# PSPS_AVNC_SRD_fullBoard-2020-09-19.net
KiCad netlist of a schematic drawn in EAGLE
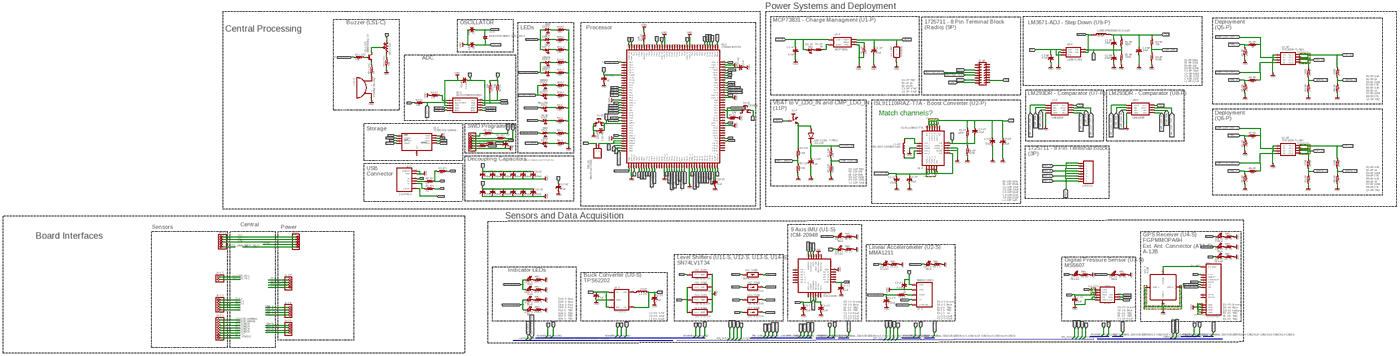
[diagram p0: schematic, sheet 1, overview]
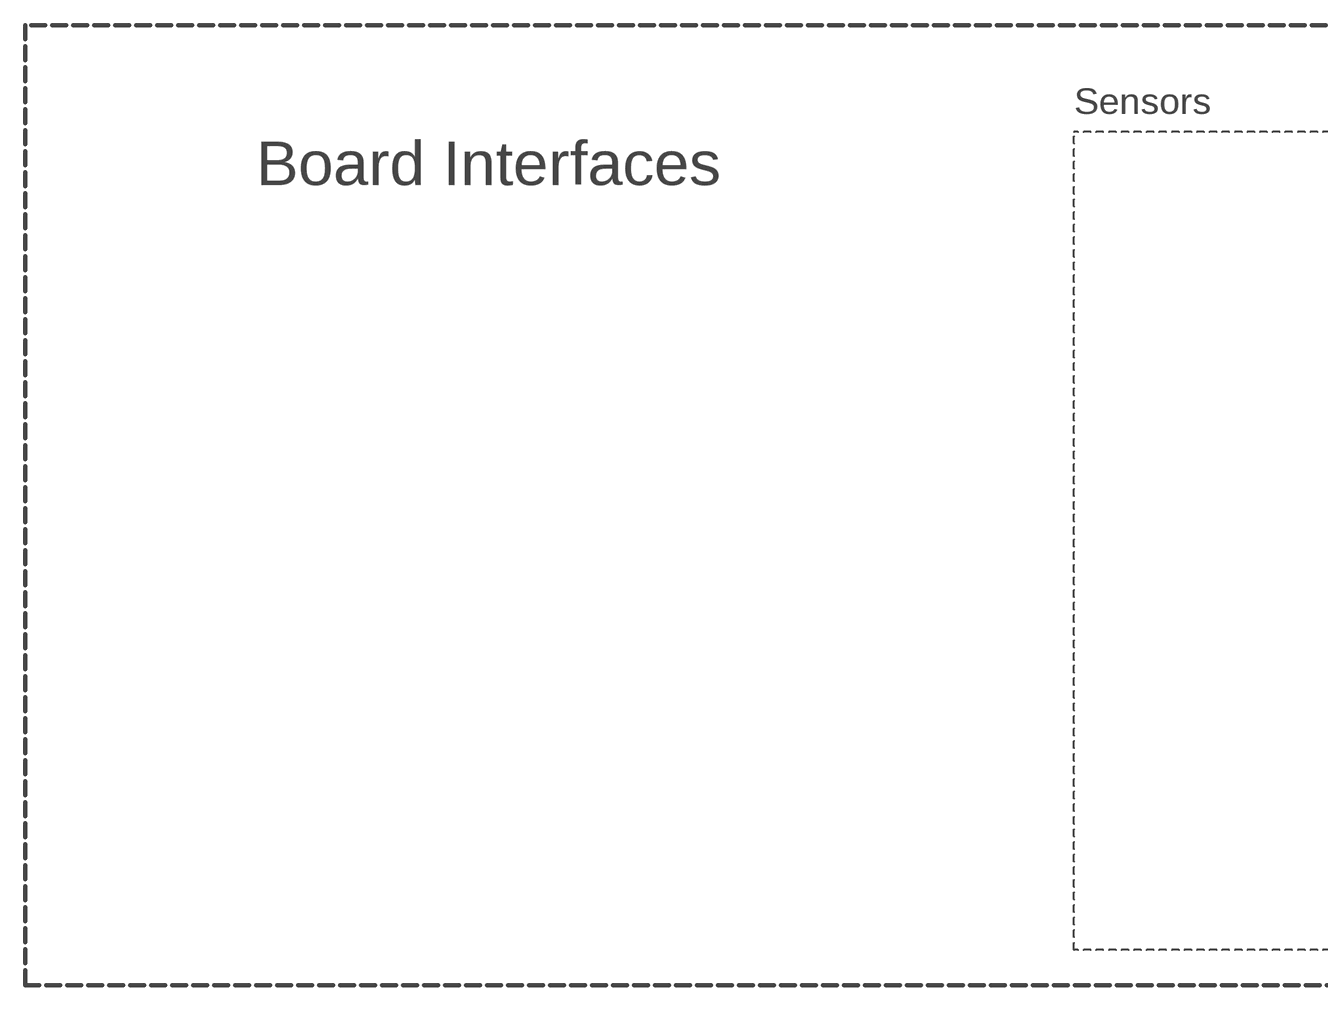
[diagram p1: schematic, sheet 1, part 1 of 4]
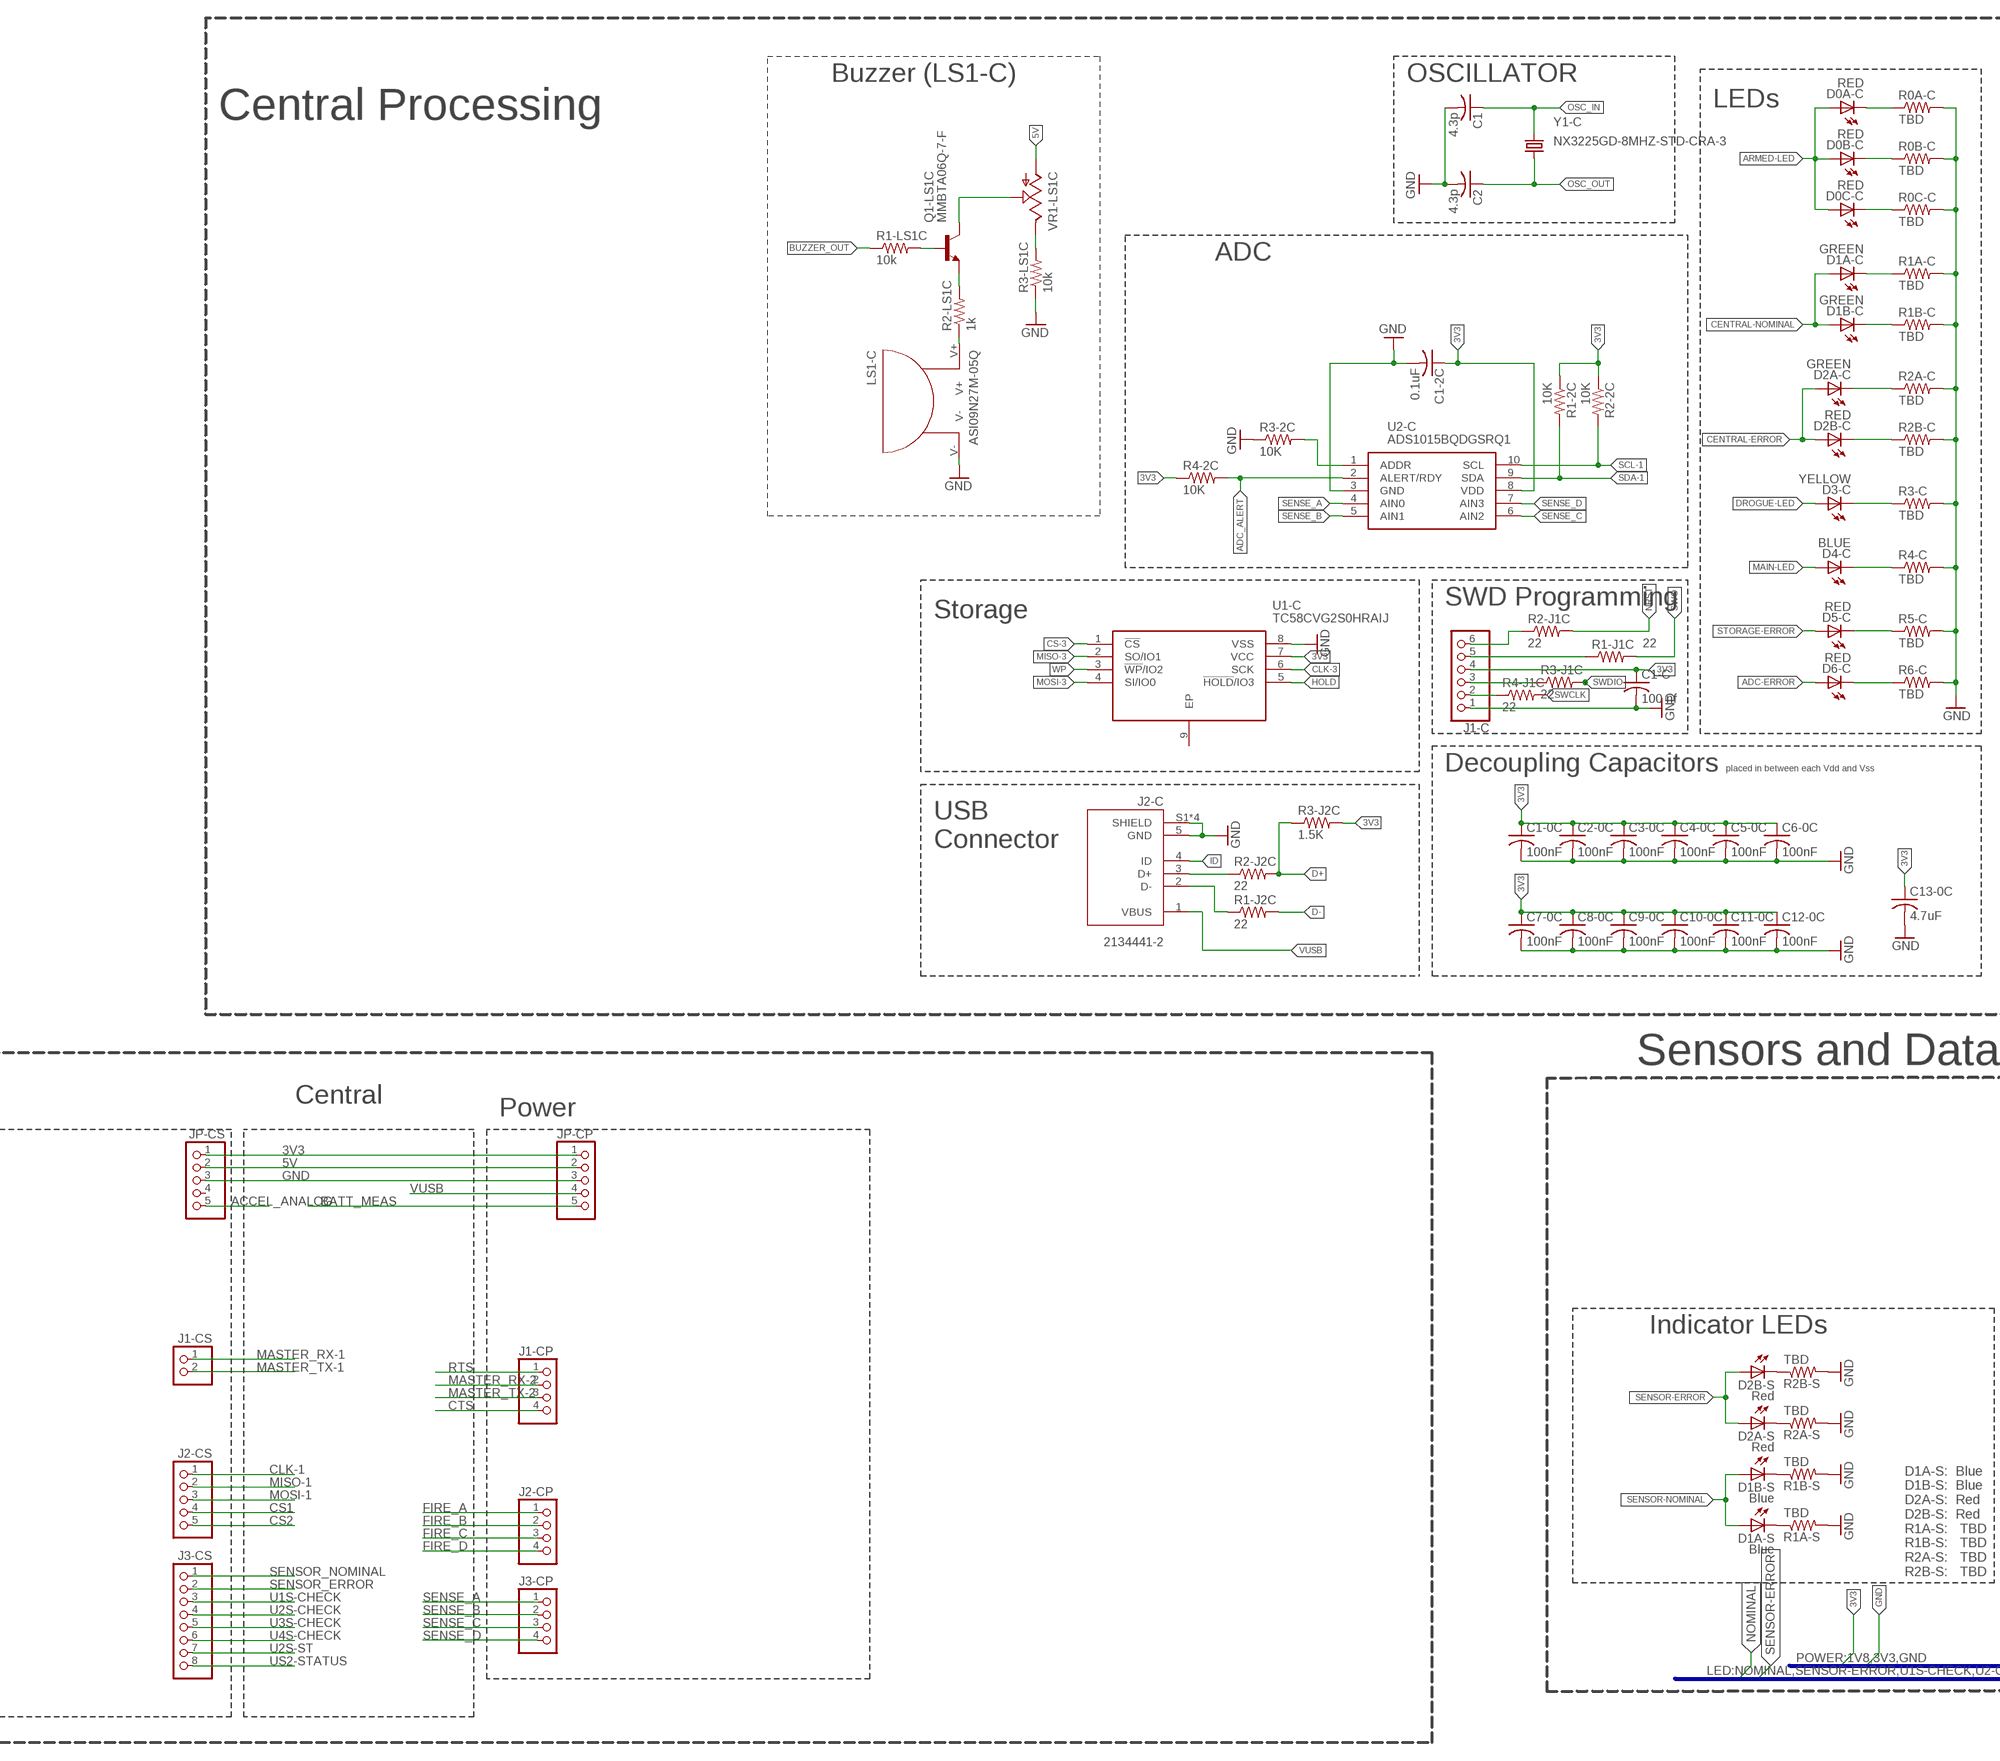
[diagram p2: schematic, sheet 1, part 2 of 4]
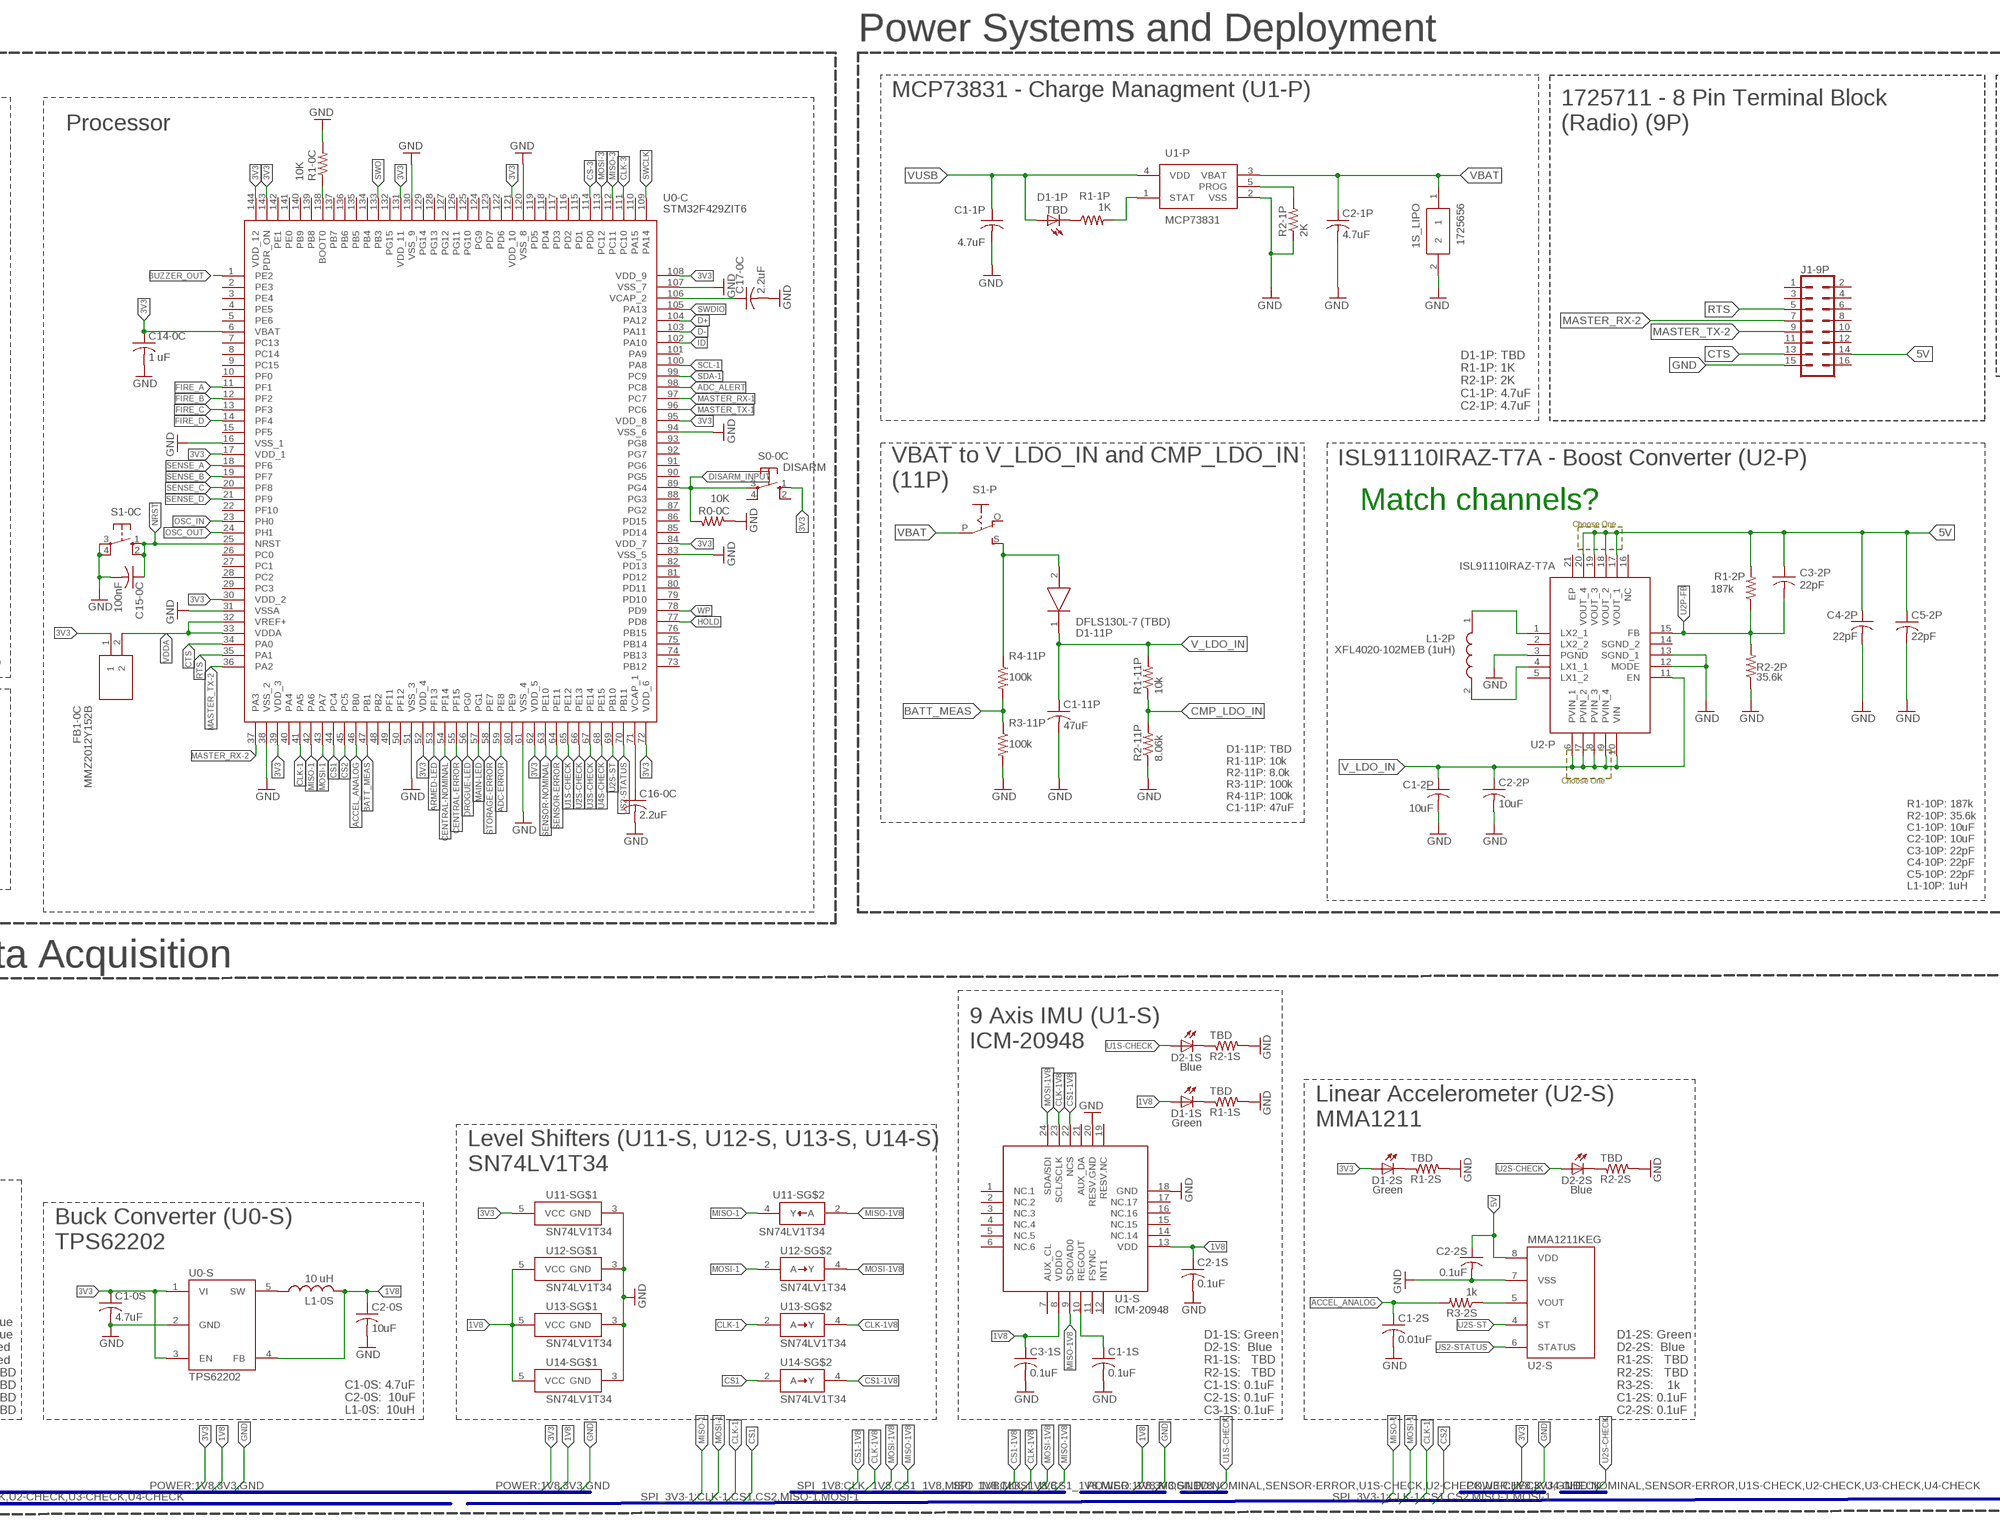
[diagram p3: schematic, sheet 1, part 3 of 4]
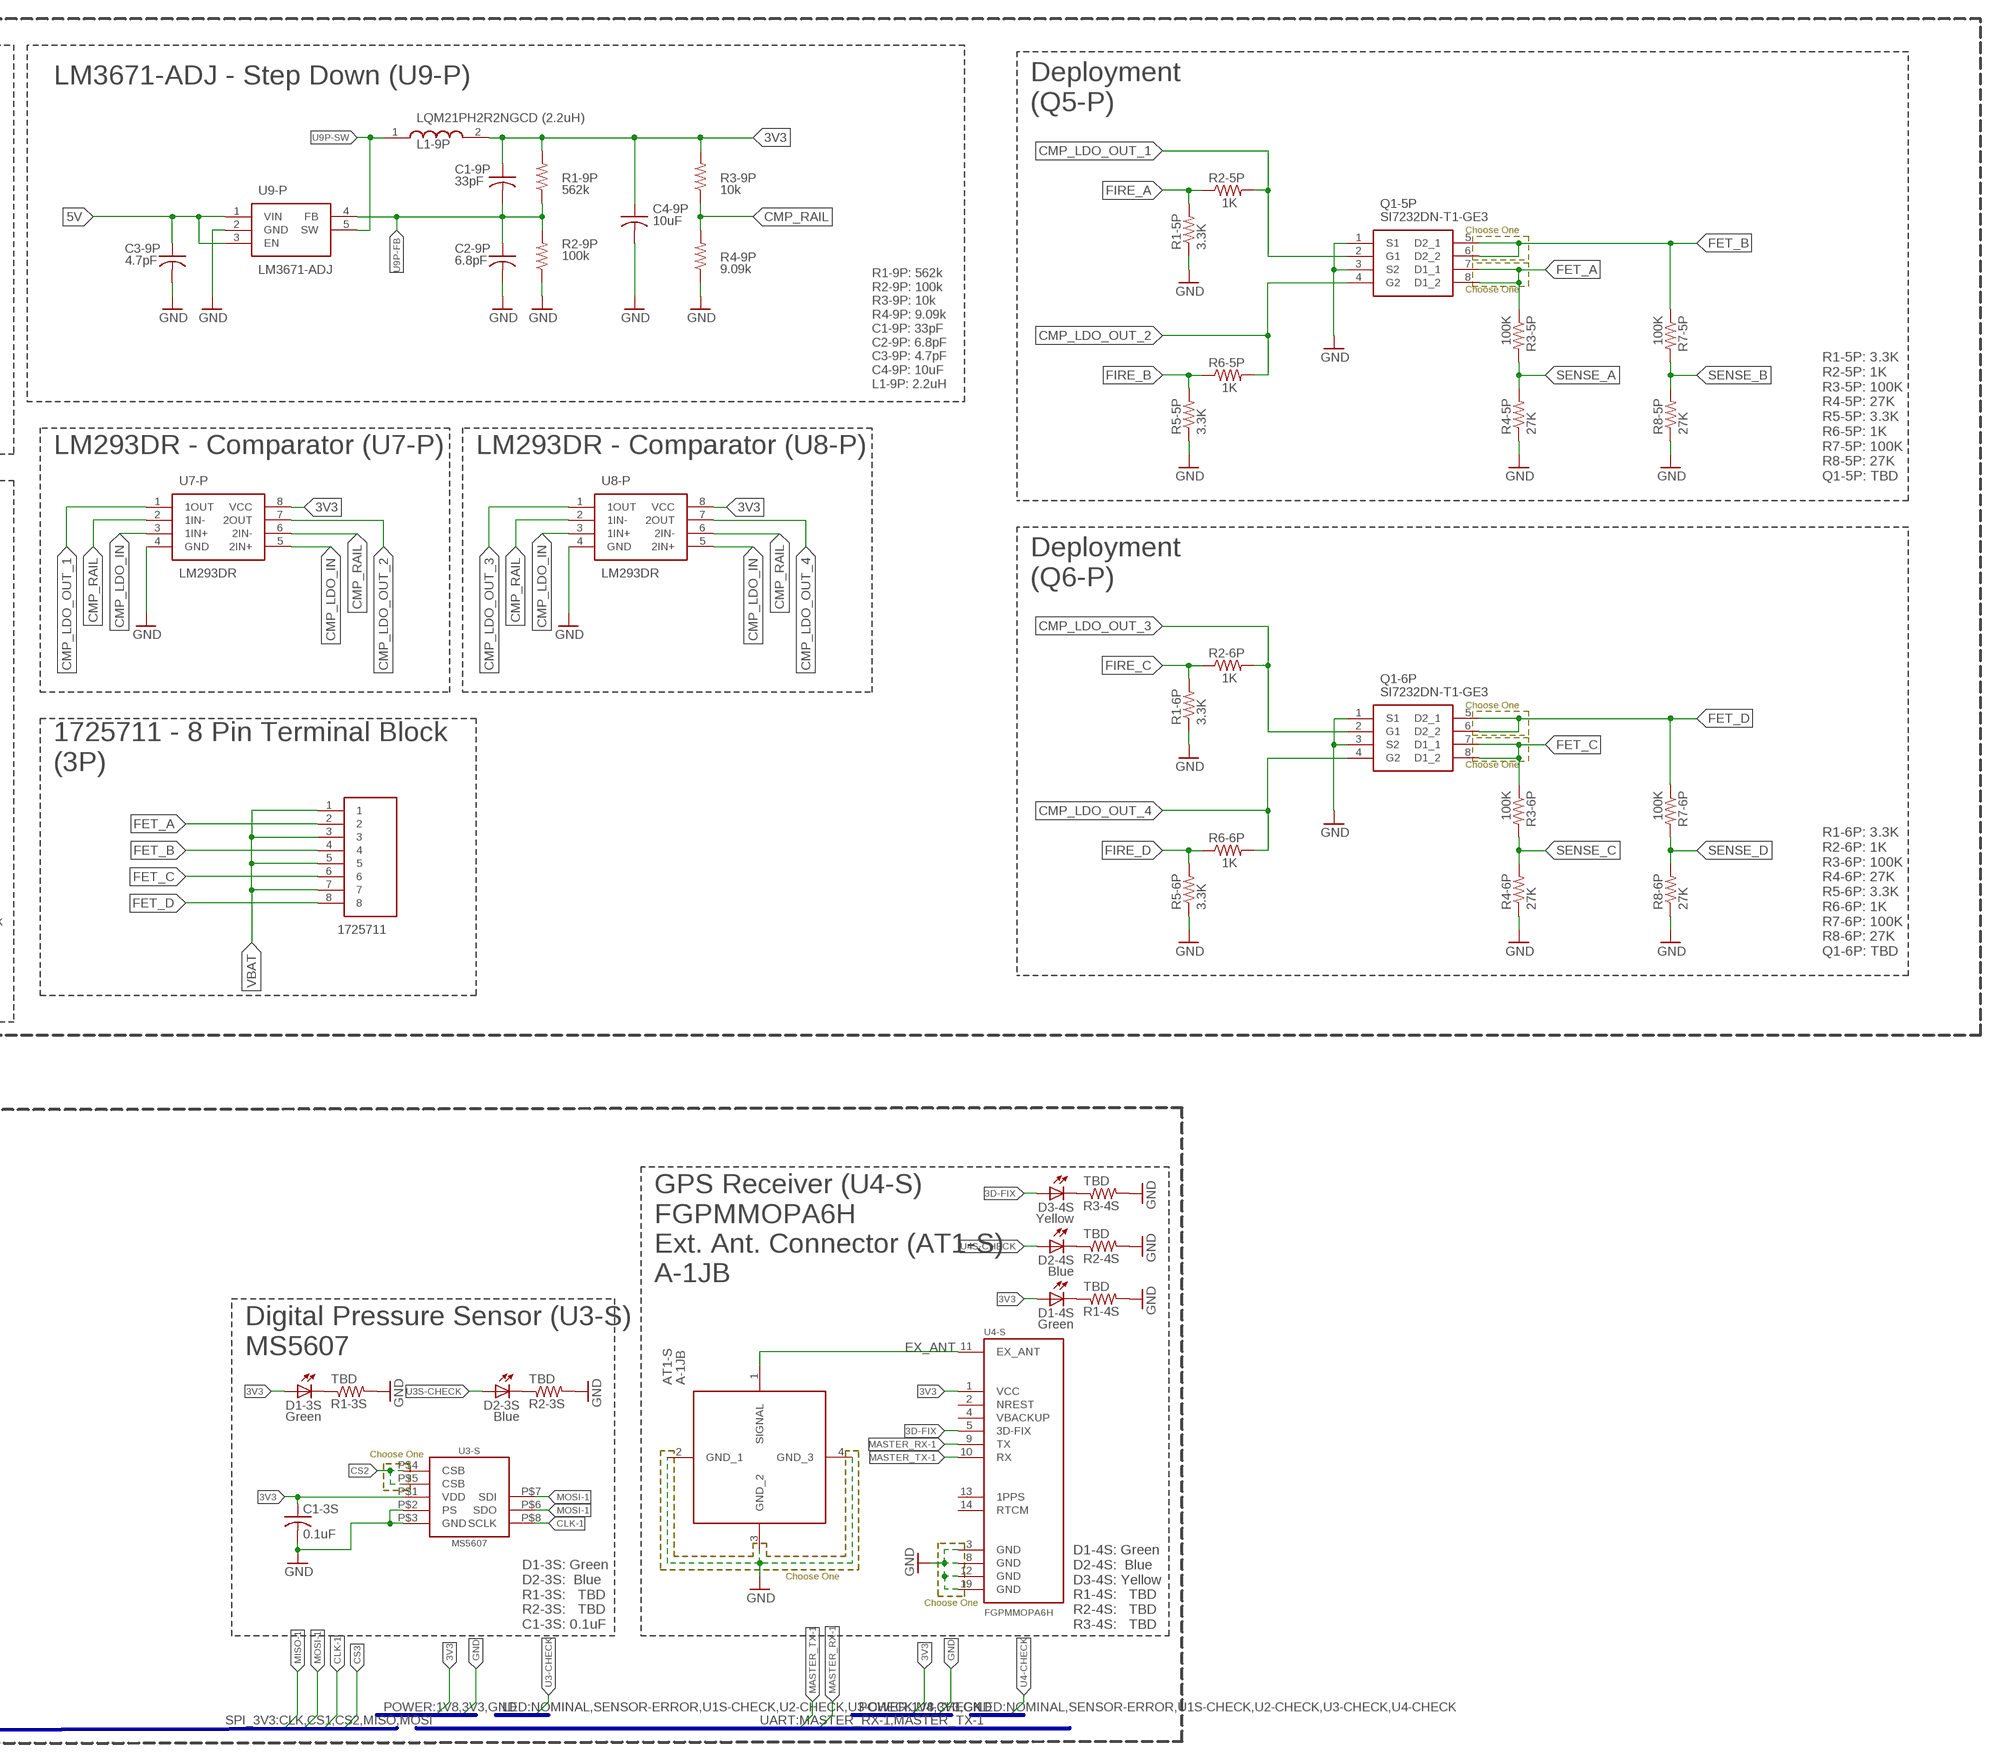
[diagram p4: schematic, sheet 1, part 4 of 4]

(export (version "E")
  (design (tool "Eeschema 10.0.6"))
  (components
    (comp (ref "1S_LIPO")
      (value "1725656")
      (footprint "eagle-import:1725656")
      (fields (field (name "MOUSER_PART_NUMBER") "651-1725656"))
      (libsource (lib "eagle-import") (part "1725656"))
    )
    (comp (ref "AT1-S")
      (value "A-1JB")
      (footprint "eagle-import:A1JB")
      (fields (field (name "MOUSER_PART_NUMBER") "523-A-1JB"))
      (libsource (lib "eagle-import") (part "A-1JB"))
    )
    (comp (ref "C1")
      (value "4.3p")
      (footprint "eagle-import:C0805")
      (libsource (lib "eagle-import") (part "rcl_334_C-USC0805"))
    )
    (comp (ref "C1-0C")
      (value "100nF")
      (footprint "eagle-import:C0805")
      (libsource (lib "eagle-import") (part "rcl_334_C-USC0805"))
    )
    (comp (ref "C1-0S")
      (value "4.7uF")
      (footprint "eagle-import:C0805")
      (libsource (lib "eagle-import") (part "resistor_348_C-USC0805"))
    )
    (comp (ref "C1-1P")
      (value "4.7uF")
      (footprint "eagle-import:C0805")
      (libsource (lib "eagle-import") (part "resistor_348_C-USC0805"))
    )
    (comp (ref "C1-1S")
      (value "0.1uF")
      (footprint "eagle-import:C0805")
      (libsource (lib "eagle-import") (part "resistor_348_C-USC0805"))
    )
    (comp (ref "C1-2C")
      (value "0.1uF")
      (footprint "eagle-import:C0805")
      (libsource (lib "eagle-import") (part "rcl_334_C-USC0805"))
    )
    (comp (ref "C1-2P")
      (value "10uF")
      (footprint "eagle-import:C0805")
      (libsource (lib "eagle-import") (part "resistor_348_C-USC0805"))
    )
    (comp (ref "C1-2S")
      (value "0.01uF")
      (footprint "eagle-import:C0805")
      (libsource (lib "eagle-import") (part "resistor_348_C-USC0805"))
    )
    (comp (ref "C1-3S")
      (value "0.1uF")
      (footprint "eagle-import:C0805")
      (libsource (lib "eagle-import") (part "resistor_348_C-USC0805"))
    )
    (comp (ref "C1-9P")
      (value "33pF")
      (footprint "eagle-import:C0805")
      (libsource (lib "eagle-import") (part "resistor_348_C-USC0805"))
    )
    (comp (ref "C1-11P")
      (value "47uF")
      (footprint "eagle-import:C0805")
      (libsource (lib "eagle-import") (part "resistor_348_C-USC0805"))
    )
    (comp (ref "C1-C")
      (value "100 nf")
      (footprint "eagle-import:C0805")
      (libsource (lib "eagle-import") (part "rcl_334_C-USC0805"))
    )
    (comp (ref "C2")
      (value "4.3p")
      (footprint "eagle-import:C0805")
      (libsource (lib "eagle-import") (part "rcl_334_C-USC0805"))
    )
    (comp (ref "C2-0C")
      (value "100nF")
      (footprint "eagle-import:C0805")
      (libsource (lib "eagle-import") (part "rcl_334_C-USC0805"))
    )
    (comp (ref "C2-0S")
      (value "10uF")
      (footprint "eagle-import:C0805")
      (libsource (lib "eagle-import") (part "resistor_348_C-USC0805"))
    )
    (comp (ref "C2-1P")
      (value "4.7uF")
      (footprint "eagle-import:C0805")
      (libsource (lib "eagle-import") (part "resistor_348_C-USC0805"))
    )
    (comp (ref "C2-1S")
      (value "0.1uF")
      (footprint "eagle-import:C0805")
      (libsource (lib "eagle-import") (part "resistor_348_C-USC0805"))
    )
    (comp (ref "C2-2P")
      (value "10uF")
      (footprint "eagle-import:C0805")
      (libsource (lib "eagle-import") (part "C-USC0805"))
    )
    (comp (ref "C2-2S")
      (value "0.1uF")
      (footprint "eagle-import:C0805")
      (libsource (lib "eagle-import") (part "resistor_348_C-USC0805"))
    )
    (comp (ref "C2-9P")
      (value "6.8pF")
      (footprint "eagle-import:C0805")
      (libsource (lib "eagle-import") (part "resistor_348_C-USC0805"))
    )
    (comp (ref "C3-0C")
      (value "100nF")
      (footprint "eagle-import:C0805")
      (libsource (lib "eagle-import") (part "rcl_334_C-USC0805"))
    )
    (comp (ref "C3-1S")
      (value "0.1uF")
      (footprint "eagle-import:C0805")
      (libsource (lib "eagle-import") (part "resistor_348_C-USC0805"))
    )
    (comp (ref "C3-2P")
      (value "22pF")
      (footprint "eagle-import:C0805")
      (libsource (lib "eagle-import") (part "resistor_348_C-USC0805"))
    )
    (comp (ref "C3-9P")
      (value "4.7pF")
      (footprint "eagle-import:C0805")
      (libsource (lib "eagle-import") (part "resistor_348_C-USC0805"))
    )
    (comp (ref "C4-0C")
      (value "100nF")
      (footprint "eagle-import:C0805")
      (libsource (lib "eagle-import") (part "rcl_334_C-USC0805"))
    )
    (comp (ref "C4-2P")
      (value "22pF")
      (footprint "eagle-import:C0805")
      (fields (field (name "SPICEPREFIX") "C"))
      (libsource (lib "eagle-import") (part "resistor_348_C-USC0805"))
    )
    (comp (ref "C4-9P")
      (value "10uF")
      (footprint "eagle-import:C0805")
      (libsource (lib "eagle-import") (part "resistor_348_C-USC0805"))
    )
    (comp (ref "C5-0C")
      (value "100nF")
      (footprint "eagle-import:C0805")
      (libsource (lib "eagle-import") (part "rcl_334_C-USC0805"))
    )
    (comp (ref "C5-2P")
      (value "22pF")
      (footprint "eagle-import:C0805")
      (libsource (lib "eagle-import") (part "C-USC0805"))
    )
    (comp (ref "C6-0C")
      (value "100nF")
      (footprint "eagle-import:C0805")
      (libsource (lib "eagle-import") (part "rcl_334_C-USC0805"))
    )
    (comp (ref "C7-0C")
      (value "100nF")
      (footprint "eagle-import:C0805")
      (libsource (lib "eagle-import") (part "rcl_334_C-USC0805"))
    )
    (comp (ref "C8-0C")
      (value "100nF")
      (footprint "eagle-import:C0805")
      (libsource (lib "eagle-import") (part "rcl_334_C-USC0805"))
    )
    (comp (ref "C9-0C")
      (value "100nF")
      (footprint "eagle-import:C0805")
      (libsource (lib "eagle-import") (part "rcl_334_C-USC0805"))
    )
    (comp (ref "C10-0C")
      (value "100nF")
      (footprint "eagle-import:C0805")
      (libsource (lib "eagle-import") (part "rcl_334_C-USC0805"))
    )
    (comp (ref "C11-0C")
      (value "100nF")
      (footprint "eagle-import:C0805")
      (libsource (lib "eagle-import") (part "rcl_334_C-USC0805"))
    )
    (comp (ref "C12-0C")
      (value "100nF")
      (footprint "eagle-import:C0805")
      (libsource (lib "eagle-import") (part "rcl_334_C-USC0805"))
    )
    (comp (ref "C13-0C")
      (value "4.7uF")
      (footprint "eagle-import:C0805")
      (libsource (lib "eagle-import") (part "rcl_334_C-USC0805"))
    )
    (comp (ref "C14-0C")
      (value "1 uF")
      (footprint "eagle-import:C0805")
      (libsource (lib "eagle-import") (part "rcl_334_C-USC0805"))
    )
    (comp (ref "C15-0C")
      (value "100nF")
      (footprint "eagle-import:C0805")
      (libsource (lib "eagle-import") (part "rcl_334_C-USC0805"))
    )
    (comp (ref "C16-0C")
      (value "2.2uF")
      (footprint "eagle-import:C0805")
      (libsource (lib "eagle-import") (part "rcl_334_C-USC0805"))
    )
    (comp (ref "C17-0C")
      (value "2.2uF")
      (footprint "eagle-import:C0805")
      (libsource (lib "eagle-import") (part "rcl_334_C-USC0805"))
    )
    (comp (ref "D0A-C")
      (value "RED")
      (footprint "eagle-import:CHIPLED_0805")
      (libsource (lib "eagle-import") (part "adafruit_420_LEDCHIPLED_0805"))
    )
    (comp (ref "D0B-C")
      (value "RED")
      (footprint "eagle-import:CHIPLED_0805")
      (libsource (lib "eagle-import") (part "adafruit_420_LEDCHIPLED_0805"))
    )
    (comp (ref "D0C-C")
      (value "RED")
      (footprint "eagle-import:CHIPLED_0805")
      (libsource (lib "eagle-import") (part "adafruit_420_LEDCHIPLED_0805"))
    )
    (comp (ref "D1-1P")
      (value "TBD")
      (footprint "eagle-import:CHIPLED_0805")
      (libsource (lib "eagle-import") (part "adafruit_420_LEDCHIPLED_0805"))
    )
    (comp (ref "D1-1S")
      (value "Green")
      (footprint "eagle-import:CHIPLED_0805")
      (libsource (lib "eagle-import") (part "LEDCHIPLED_0805"))
    )
    (comp (ref "D1-2S")
      (value "Green")
      (footprint "eagle-import:CHIPLED_0805")
      (libsource (lib "eagle-import") (part "LEDCHIPLED_0805"))
    )
    (comp (ref "D1-3S")
      (value "Green")
      (footprint "eagle-import:CHIPLED_0805")
      (libsource (lib "eagle-import") (part "LEDCHIPLED_0805"))
    )
    (comp (ref "D1-4S")
      (value "Green")
      (footprint "eagle-import:CHIPLED_0805")
      (libsource (lib "eagle-import") (part "LEDCHIPLED_0805"))
    )
    (comp (ref "D1-11P")
      (value "DFLS130L-7 (TBD)")
      (footprint "eagle-import:POWERDI_123")
      (fields
        (field (name "MANUFACTURER_PART_NUMBER") "DFLS130L-7")
        (field (name "MOUSER_PART_NUMBER") "621-DFLS130L")
      )
      (libsource (lib "eagle-import") (part "DFLS130L-7"))
    )
    (comp (ref "D1A-C")
      (value "GREEN")
      (footprint "eagle-import:CHIPLED_0805")
      (libsource (lib "eagle-import") (part "adafruit_420_LEDCHIPLED_0805"))
    )
    (comp (ref "D1A-S")
      (value "Blue")
      (footprint "eagle-import:CHIPLED_0805")
      (libsource (lib "eagle-import") (part "LEDCHIPLED_0805"))
    )
    (comp (ref "D1B-C")
      (value "GREEN")
      (footprint "eagle-import:CHIPLED_0805")
      (libsource (lib "eagle-import") (part "adafruit_420_LEDCHIPLED_0805"))
    )
    (comp (ref "D1B-S")
      (value "Blue")
      (footprint "eagle-import:CHIPLED_0805")
      (libsource (lib "eagle-import") (part "LEDCHIPLED_0805"))
    )
    (comp (ref "D2-1S")
      (value "Blue")
      (footprint "eagle-import:CHIPLED_0805")
      (libsource (lib "eagle-import") (part "LEDCHIPLED_0805"))
    )
    (comp (ref "D2-2S")
      (value "Blue")
      (footprint "eagle-import:CHIPLED_0805")
      (libsource (lib "eagle-import") (part "LEDCHIPLED_0805"))
    )
    (comp (ref "D2-3S")
      (value "Blue")
      (footprint "eagle-import:CHIPLED_0805")
      (libsource (lib "eagle-import") (part "LEDCHIPLED_0805"))
    )
    (comp (ref "D2-4S")
      (value "Blue")
      (footprint "eagle-import:CHIPLED_0805")
      (libsource (lib "eagle-import") (part "LEDCHIPLED_0805"))
    )
    (comp (ref "D2A-C")
      (value "GREEN")
      (footprint "eagle-import:CHIPLED_0805")
      (libsource (lib "eagle-import") (part "adafruit_420_LEDCHIPLED_0805"))
    )
    (comp (ref "D2A-S")
      (value "Red")
      (footprint "eagle-import:CHIPLED_0805")
      (libsource (lib "eagle-import") (part "LEDCHIPLED_0805"))
    )
    (comp (ref "D2B-C")
      (value "RED")
      (footprint "eagle-import:CHIPLED_0805")
      (libsource (lib "eagle-import") (part "adafruit_420_LEDCHIPLED_0805"))
    )
    (comp (ref "D2B-S")
      (value "Red")
      (footprint "eagle-import:CHIPLED_0805")
      (libsource (lib "eagle-import") (part "LEDCHIPLED_0805"))
    )
    (comp (ref "D3-4S")
      (value "Yellow")
      (footprint "eagle-import:CHIPLED_0805")
      (libsource (lib "eagle-import") (part "LEDCHIPLED_0805"))
    )
    (comp (ref "D3-C")
      (value "YELLOW")
      (footprint "eagle-import:CHIPLED_0805")
      (libsource (lib "eagle-import") (part "adafruit_420_LEDCHIPLED_0805"))
    )
    (comp (ref "D4-C")
      (value "BLUE")
      (footprint "eagle-import:CHIPLED_0805")
      (libsource (lib "eagle-import") (part "adafruit_420_LEDCHIPLED_0805"))
    )
    (comp (ref "D5-C")
      (value "RED")
      (footprint "eagle-import:CHIPLED_0805")
      (libsource (lib "eagle-import") (part "adafruit_420_LEDCHIPLED_0805"))
    )
    (comp (ref "D6-C")
      (value "RED")
      (footprint "eagle-import:CHIPLED_0805")
      (libsource (lib "eagle-import") (part "adafruit_420_LEDCHIPLED_0805"))
    )
    (comp (ref "FB1-0C")
      (value "MMZ2012Y152B")
      (footprint "eagle-import:BEADC2012X105N")
      (fields (field (name "MOUSER_PART_NUMBER") "810-MMZ2012Y152B"))
      (libsource (lib "eagle-import") (part "MMZ2012Y152B"))
    )
    (comp (ref "J1-9P")
      (value "CONN_08X2")
      (footprint "eagle-import:2X8")
      (libsource (lib "eagle-import") (part "CONN_08X2"))
    )
    (comp (ref "J1-C")
      (value "PINHD-1X6")
      (footprint "eagle-import:1X06")
      (libsource (lib "eagle-import") (part "PINHD-1X6"))
    )
    (comp (ref "J1-CP")
      (value "PINHD-1X4")
      (footprint "eagle-import:1X04")
      (libsource (lib "eagle-import") (part "PINHD-1X4"))
    )
    (comp (ref "J1-CS")
      (value "PINHD-1X2")
      (footprint "eagle-import:1X02")
      (libsource (lib "eagle-import") (part "PINHD-1X2"))
    )
    (comp (ref "J2-C")
      (value "2134441-2")
      (footprint "eagle-import:TE_2134441-2")
      (fields (field (name "DIGI-KEY_PART_NUMBER") "A118104CT-ND") (field (name "MF") "TE Connectivity"))
      (libsource (lib "eagle-import") (part "2134441-2"))
    )
    (comp (ref "J2-CP")
      (value "PINHD-1X4")
      (footprint "eagle-import:1X04")
      (libsource (lib "eagle-import") (part "PINHD-1X4"))
    )
    (comp (ref "J2-CS")
      (value "PINHD-1X5")
      (footprint "eagle-import:1X05")
      (libsource (lib "eagle-import") (part "PINHD-1X5"))
    )
    (comp (ref "J2-P")
      (value "1725711")
      (footprint "eagle-import:1725711")
      (fields (field (name "MOUSER_PART_NUMBER") "651-1725711"))
      (libsource (lib "eagle-import") (part "1725711"))
    )
    (comp (ref "J3-CP")
      (value "PINHD-1X4")
      (footprint "eagle-import:1X04")
      (libsource (lib "eagle-import") (part "PINHD-1X4"))
    )
    (comp (ref "J3-CS")
      (value "PINHD-1X8")
      (footprint "eagle-import:1X08")
      (libsource (lib "eagle-import") (part "PINHD-1X8"))
    )
    (comp (ref "JP-CP")
      (value "PINHD-1X5")
      (footprint "eagle-import:1X05")
      (libsource (lib "eagle-import") (part "PINHD-1X5"))
    )
    (comp (ref "JP-CS")
      (value "PINHD-1X5")
      (footprint "eagle-import:1X05")
      (libsource (lib "eagle-import") (part "PINHD-1X5"))
    )
    (comp (ref "L1-0S")
      (value "10 uH")
      (footprint "eagle-import:PF0560NL")
      (libsource (lib "eagle-import") (part "PF0560.103NLT"))
    )
    (comp (ref "L1-2P")
      (value "XFL4020-102MEB (1uH)")
      (footprint "eagle-import:XFL4020")
      (fields
        (field (name "MANUFACTURER_PART_NUMBER") "XFL4020-102MEB")
        (field (name "MOUSER_PART_NUMBER") "994-XFL4020-102MEB")
      )
      (libsource (lib "eagle-import") (part "XFL4020-102MEB"))
    )
    (comp (ref "L1-9P")
      (value "LQM21PH2R2NGCD (2.2uH)")
      (footprint "eagle-import:INDC2012X100N")
      (fields
        (field (name "MANUFACTURER_PART_NUMBER") "LQM21PH2R2NGCD")
        (field (name "MOUSER_PART_NUMBER") "81-LQM21PH2R2NGCD")
      )
      (libsource (lib "eagle-import") (part "LQM21PH2R2NGCD"))
    )
    (comp (ref "LS1-C")
      (value "ASI09N27M-05Q")
      (footprint "eagle-import:ASI09N27M-05Q")
      (libsource (lib "eagle-import") (part "ASI09N27M-05Q"))
    )
    (comp (ref "Q1-5P")
      (value "SI7232DN-T1-GE3")
      (footprint "eagle-import:POWERPAK-1212-8")
      (fields (field (name "MOUSER_PART_NUMBER") "781-SI7232DN-GE3"))
      (libsource (lib "eagle-import") (part "SI7232DN-T1-GE3"))
    )
    (comp (ref "Q1-6P")
      (value "SI7232DN-T1-GE3")
      (footprint "eagle-import:POWERPAK-1212-8")
      (fields (field (name "MOUSER_PART_NUMBER") "781-SI7232DN-GE3"))
      (libsource (lib "eagle-import") (part "SI7232DN-T1-GE3"))
    )
    (comp (ref "Q1-LS1C")
      (value "MMBTA06Q-7-F")
      (footprint "eagle-import:SOT23")
      (libsource (lib "eagle-import") (part "NPN_TRANSISTOR"))
    )
    (comp (ref "R0-0C")
      (value "10K")
      (footprint "eagle-import:R0805")
      (libsource (lib "eagle-import") (part "rcl_334_R-US_R0805"))
    )
    (comp (ref "R0A-C")
      (value "TBD")
      (footprint "eagle-import:M0805")
      (libsource (lib "eagle-import") (part "rcl_334_R-US_M0805"))
    )
    (comp (ref "R0B-C")
      (value "TBD")
      (footprint "eagle-import:M0805")
      (libsource (lib "eagle-import") (part "rcl_334_R-US_M0805"))
    )
    (comp (ref "R0C-C")
      (value "TBD")
      (footprint "eagle-import:M0805")
      (libsource (lib "eagle-import") (part "rcl_334_R-US_M0805"))
    )
    (comp (ref "R1-0C")
      (value "10K")
      (footprint "eagle-import:R0805")
      (libsource (lib "eagle-import") (part "rcl_334_R-US_R0805"))
    )
    (comp (ref "R1-1P")
      (value "1K")
      (footprint "eagle-import:R0805")
      (libsource (lib "eagle-import") (part "resistor_348_R-US_R0805"))
    )
    (comp (ref "R1-1S")
      (value "TBD")
      (footprint "eagle-import:R0805")
      (libsource (lib "eagle-import") (part "resistor_348_R-US_R0805"))
    )
    (comp (ref "R1-2C")
      (value "10K")
      (footprint "eagle-import:R0805")
      (libsource (lib "eagle-import") (part "rcl_334_R-US_R0805"))
    )
    (comp (ref "R1-2P")
      (value "187k")
      (footprint "eagle-import:R0805")
      (libsource (lib "eagle-import") (part "resistor_348_R-US_R0805"))
    )
    (comp (ref "R1-2S")
      (value "TBD")
      (footprint "eagle-import:R0805")
      (libsource (lib "eagle-import") (part "resistor_348_R-US_R0805"))
    )
    (comp (ref "R1-3S")
      (value "TBD")
      (footprint "eagle-import:R0805")
      (libsource (lib "eagle-import") (part "resistor_348_R-US_R0805"))
    )
    (comp (ref "R1-4S")
      (value "TBD")
      (footprint "eagle-import:R0805")
      (libsource (lib "eagle-import") (part "resistor_348_R-US_R0805"))
    )
    (comp (ref "R1-5P")
      (value "3.3K")
      (footprint "eagle-import:M0805")
      (libsource (lib "eagle-import") (part "rcl_334_R-US_M0805"))
    )
    (comp (ref "R1-6P")
      (value "3.3K")
      (footprint "eagle-import:M0805")
      (libsource (lib "eagle-import") (part "rcl_334_R-US_M0805"))
    )
    (comp (ref "R1-9P")
      (value "562k")
      (footprint "eagle-import:R0805")
      (libsource (lib "eagle-import") (part "resistor_348_R-US_R0805"))
    )
    (comp (ref "R1-11P")
      (value "10k")
      (footprint "eagle-import:R0805")
      (libsource (lib "eagle-import") (part "resistor_348_R-US_R0805"))
    )
    (comp (ref "R1-J1C")
      (value "22")
      (footprint "eagle-import:M0805")
      (libsource (lib "eagle-import") (part "rcl_334_R-US_M0805"))
    )
    (comp (ref "R1-J2C")
      (value "22")
      (footprint "eagle-import:M0805")
      (libsource (lib "eagle-import") (part "rcl_334_R-US_M0805"))
    )
    (comp (ref "R1-LS1C")
      (value "10k")
      (footprint "eagle-import:R0805")
      (libsource (lib "eagle-import") (part "resistor_348_R-US_R0805"))
    )
    (comp (ref "R1A-C")
      (value "TBD")
      (footprint "eagle-import:M0805")
      (libsource (lib "eagle-import") (part "rcl_334_R-US_M0805"))
    )
    (comp (ref "R1A-S")
      (value "TBD")
      (footprint "eagle-import:R0805")
      (libsource (lib "eagle-import") (part "resistor_348_R-US_R0805"))
    )
    (comp (ref "R1B-C")
      (value "TBD")
      (footprint "eagle-import:M0805")
      (libsource (lib "eagle-import") (part "rcl_334_R-US_M0805"))
    )
    (comp (ref "R1B-S")
      (value "TBD")
      (footprint "eagle-import:R0805")
      (libsource (lib "eagle-import") (part "resistor_348_R-US_R0805"))
    )
    (comp (ref "R2-1P")
      (value "2K")
      (footprint "eagle-import:R0805")
      (libsource (lib "eagle-import") (part "resistor_348_R-US_R0805"))
    )
    (comp (ref "R2-1S")
      (value "TBD")
      (footprint "eagle-import:R0805")
      (libsource (lib "eagle-import") (part "resistor_348_R-US_R0805"))
    )
    (comp (ref "R2-2C")
      (value "10K")
      (footprint "eagle-import:R0805")
      (libsource (lib "eagle-import") (part "rcl_334_R-US_R0805"))
    )
    (comp (ref "R2-2P")
      (value "35.6k")
      (footprint "eagle-import:R0805")
      (libsource (lib "eagle-import") (part "resistor_348_R-US_R0805"))
    )
    (comp (ref "R2-2S")
      (value "TBD")
      (footprint "eagle-import:R0805")
      (libsource (lib "eagle-import") (part "resistor_348_R-US_R0805"))
    )
    (comp (ref "R2-3S")
      (value "TBD")
      (footprint "eagle-import:R0805")
      (libsource (lib "eagle-import") (part "resistor_348_R-US_R0805"))
    )
    (comp (ref "R2-4S")
      (value "TBD")
      (footprint "eagle-import:R0805")
      (libsource (lib "eagle-import") (part "resistor_348_R-US_R0805"))
    )
    (comp (ref "R2-5P")
      (value "1K")
      (footprint "eagle-import:M0805")
      (libsource (lib "eagle-import") (part "rcl_334_R-US_M0805"))
    )
    (comp (ref "R2-6P")
      (value "1K")
      (footprint "eagle-import:M0805")
      (libsource (lib "eagle-import") (part "rcl_334_R-US_M0805"))
    )
    (comp (ref "R2-9P")
      (value "100k")
      (footprint "eagle-import:R0805")
      (libsource (lib "eagle-import") (part "resistor_348_R-US_R0805"))
    )
    (comp (ref "R2-11P")
      (value "8.06k")
      (footprint "eagle-import:R0805")
      (libsource (lib "eagle-import") (part "resistor_348_R-US_R0805"))
    )
    (comp (ref "R2-J1C")
      (value "22")
      (footprint "eagle-import:M0805")
      (libsource (lib "eagle-import") (part "rcl_334_R-US_M0805"))
    )
    (comp (ref "R2-J2C")
      (value "22")
      (footprint "eagle-import:M0805")
      (libsource (lib "eagle-import") (part "rcl_334_R-US_M0805"))
    )
    (comp (ref "R2-LS1C")
      (value "1k")
      (footprint "eagle-import:R0805")
      (libsource (lib "eagle-import") (part "resistor_348_R-US_R0805"))
    )
    (comp (ref "R2A-C")
      (value "TBD")
      (footprint "eagle-import:M0805")
      (libsource (lib "eagle-import") (part "rcl_334_R-US_M0805"))
    )
    (comp (ref "R2A-S")
      (value "TBD")
      (footprint "eagle-import:R0805")
      (libsource (lib "eagle-import") (part "resistor_348_R-US_R0805"))
    )
    (comp (ref "R2B-C")
      (value "TBD")
      (footprint "eagle-import:M0805")
      (libsource (lib "eagle-import") (part "rcl_334_R-US_M0805"))
    )
    (comp (ref "R2B-S")
      (value "TBD")
      (footprint "eagle-import:R0805")
      (libsource (lib "eagle-import") (part "resistor_348_R-US_R0805"))
    )
    (comp (ref "R3-2C")
      (value "10K")
      (footprint "eagle-import:R0805")
      (libsource (lib "eagle-import") (part "rcl_334_R-US_R0805"))
    )
    (comp (ref "R3-2S")
      (value "1k")
      (footprint "eagle-import:R0805")
      (libsource (lib "eagle-import") (part "resistor_348_R-US_R0805"))
    )
    (comp (ref "R3-4S")
      (value "TBD")
      (footprint "eagle-import:R0805")
      (libsource (lib "eagle-import") (part "resistor_348_R-US_R0805"))
    )
    (comp (ref "R3-5P")
      (value "100K")
      (footprint "eagle-import:M0805")
      (libsource (lib "eagle-import") (part "rcl_334_R-US_M0805"))
    )
    (comp (ref "R3-6P")
      (value "100K")
      (footprint "eagle-import:M0805")
      (libsource (lib "eagle-import") (part "rcl_334_R-US_M0805"))
    )
    (comp (ref "R3-9P")
      (value "10k")
      (footprint "eagle-import:R0805")
      (libsource (lib "eagle-import") (part "resistor_348_R-US_R0805"))
    )
    (comp (ref "R3-11P")
      (value "100k")
      (footprint "eagle-import:R0805")
      (libsource (lib "eagle-import") (part "R-US_R0805"))
    )
    (comp (ref "R3-C")
      (value "TBD")
      (footprint "eagle-import:M0805")
      (libsource (lib "eagle-import") (part "rcl_334_R-US_M0805"))
    )
    (comp (ref "R3-J1C")
      (value "22")
      (footprint "eagle-import:M0805")
      (libsource (lib "eagle-import") (part "rcl_334_R-US_M0805"))
    )
    (comp (ref "R3-J2C")
      (value "1.5K")
      (footprint "eagle-import:M0805")
      (libsource (lib "eagle-import") (part "rcl_334_R-US_M0805"))
    )
    (comp (ref "R3-LS1C")
      (value "10k")
      (footprint "eagle-import:R0805")
      (libsource (lib "eagle-import") (part "resistor_348_R-US_R0805"))
    )
    (comp (ref "R4-2C")
      (value "10K")
      (footprint "eagle-import:R0805")
      (libsource (lib "eagle-import") (part "rcl_334_R-US_R0805"))
    )
    (comp (ref "R4-5P")
      (value "27K")
      (footprint "eagle-import:M0805")
      (libsource (lib "eagle-import") (part "rcl_334_R-US_M0805"))
    )
    (comp (ref "R4-6P")
      (value "27K")
      (footprint "eagle-import:M0805")
      (libsource (lib "eagle-import") (part "rcl_334_R-US_M0805"))
    )
    (comp (ref "R4-9P")
      (value "9.09k")
      (footprint "eagle-import:R0805")
      (libsource (lib "eagle-import") (part "resistor_348_R-US_R0805"))
    )
    (comp (ref "R4-11P")
      (value "100k")
      (footprint "eagle-import:R0805")
      (libsource (lib "eagle-import") (part "R-US_R0805"))
    )
    (comp (ref "R4-C")
      (value "TBD")
      (footprint "eagle-import:M0805")
      (libsource (lib "eagle-import") (part "rcl_334_R-US_M0805"))
    )
    (comp (ref "R4-J1C")
      (value "22")
      (footprint "eagle-import:M0805")
      (libsource (lib "eagle-import") (part "rcl_334_R-US_M0805"))
    )
    (comp (ref "R5-5P")
      (value "3.3K")
      (footprint "eagle-import:M0805")
      (libsource (lib "eagle-import") (part "rcl_334_R-US_M0805"))
    )
    (comp (ref "R5-6P")
      (value "3.3K")
      (footprint "eagle-import:M0805")
      (libsource (lib "eagle-import") (part "rcl_334_R-US_M0805"))
    )
    (comp (ref "R5-C")
      (value "TBD")
      (footprint "eagle-import:M0805")
      (libsource (lib "eagle-import") (part "rcl_334_R-US_M0805"))
    )
    (comp (ref "R6-5P")
      (value "1K")
      (footprint "eagle-import:M0805")
      (libsource (lib "eagle-import") (part "rcl_334_R-US_M0805"))
    )
    (comp (ref "R6-6P")
      (value "1K")
      (footprint "eagle-import:M0805")
      (libsource (lib "eagle-import") (part "rcl_334_R-US_M0805"))
    )
    (comp (ref "R6-C")
      (value "TBD")
      (footprint "eagle-import:M0805")
      (libsource (lib "eagle-import") (part "rcl_334_R-US_M0805"))
    )
    (comp (ref "R7-5P")
      (value "100K")
      (footprint "eagle-import:M0805")
      (libsource (lib "eagle-import") (part "rcl_334_R-US_M0805"))
    )
    (comp (ref "R7-6P")
      (value "100K")
      (footprint "eagle-import:M0805")
      (libsource (lib "eagle-import") (part "rcl_334_R-US_M0805"))
    )
    (comp (ref "R8-5P")
      (value "27K")
      (footprint "eagle-import:M0805")
      (libsource (lib "eagle-import") (part "rcl_334_R-US_M0805"))
    )
    (comp (ref "R8-6P")
      (value "27K")
      (footprint "eagle-import:M0805")
      (libsource (lib "eagle-import") (part "rcl_334_R-US_M0805"))
    )
    (comp (ref "S0-0C")
      (value "DISARM")
      (footprint "eagle-import:B3F-10XX")
      (fields (field (name "MPN") "B3F-1000"))
      (libsource (lib "eagle-import") (part "10-XX"))
    )
    (comp (ref "S1-0C")
      (value "10-XX")
      (footprint "eagle-import:B3F-10XX")
      (fields (field (name "MPN") "B3F-1000"))
      (libsource (lib "eagle-import") (part "10-XX"))
    )
    (comp (ref "S1-P")
      (value "EG1218S")
      (footprint "eagle-import:EG1218")
      (libsource (lib "eagle-import") (part "EG1218S"))
    )
    (comp (ref "U0-C")
      (value "STM32F429ZIT6")
      (footprint "eagle-import:QFP50P2200X2200X160-144N")
      (fields (field (name "MOUSER_PART_NUMBER") "511-STM32F429ZIT6"))
      (libsource (lib "eagle-import") (part "STM32F429ZIT6"))
    )
    (comp (ref "U0-S")
      (value "TPS62202")
      (footprint "eagle-import:SOT95P280X145-5")
      (libsource (lib "eagle-import") (part "TPS62202"))
    )
    (comp (ref "U1-C")
      (value "TC58CVG2S0HRAIJ")
      (footprint "eagle-import:SON127P800X600X80-9N")
      (fields (field (name "MOUSER_PART_NUMBER") "757-TC58CVG2S0HRAIJ"))
      (libsource (lib "eagle-import") (part "TC58CVG2S0HRAIJ"))
    )
    (comp (ref "U1-P")
      (value "MCP73831")
      (footprint "eagle-import:SOT95P270X145-5N")
      (fields
        (field (name "MANUFACTURER_PART_NUMBER") "MCP73831T-2ACI/OT")
        (field (name "MOUSER_PART_NUMBER") "579-MCP73831T-2ACIOT")
      )
      (libsource (lib "eagle-import") (part "MCP73831T-2ACI_OT"))
    )
    (comp (ref "U1-S")
      (value "ICM-20948")
      (footprint "eagle-import:QFN40P300X300X105-25T159X175")
      (libsource (lib "eagle-import") (part "ICM-20948"))
    )
    (comp (ref "U2-C")
      (value "ADS1015BQDGSRQ1")
      (footprint "eagle-import:SOP50P490X110-10N")
      (fields (field (name "MOUSER_PART_NUMBER") "595-ADS1015BQDGSRQ1"))
      (libsource (lib "eagle-import") (part "ADS1015BQDGSRQ1"))
    )
    (comp (ref "U2-P")
      (value "ISL91110IRAZ-T7A")
      (footprint "eagle-import:QFN50P400X400X100-21N")
      (libsource (lib "eagle-import") (part "ISL91110IRAZ-T7A"))
    )
    (comp (ref "U2-S")
      (value "MMA1211KEG")
      (footprint "eagle-import:SOIC127P1041X355-16N")
      (libsource (lib "eagle-import") (part "MMA1211KEG"))
    )
    (comp (ref "U3-S")
      (value "MS5607")
      (footprint "eagle-import:MS5607")
      (libsource (lib "eagle-import") (part "MS5607"))
    )
    (comp (ref "U4-S")
      (value "FGPMMOPA6H")
      (footprint "eagle-import:SOIC127P1800X470-20N")
      (libsource (lib "eagle-import") (part "FGPMMOPA6H"))
    )
    (comp (ref "U7-P")
      (value "LM293DR")
      (footprint "eagle-import:SOIC127P600X175-8N")
      (fields (field (name "MOUSER_PART_NUMBER") "595-LM293DR"))
      (libsource (lib "eagle-import") (part "LM293DR"))
    )
    (comp (ref "U8-P")
      (value "LM293DR")
      (footprint "eagle-import:SOIC127P600X175-8N")
      (fields (field (name "MOUSER_PART_NUMBER") "595-LM293DR"))
      (libsource (lib "eagle-import") (part "LM293DR"))
    )
    (comp (ref "U9-P")
      (value "LM3671-ADJ")
      (footprint "eagle-import:SOT95P280X145-5N")
      (fields
        (field (name "MANUFACTURER_PART_NUMBER") "LM3671MFX-ADJ/NOPB")
        (field (name "MOUSER_PART_NUMBER") "926-LM3671MFXADJNOPB")
      )
      (libsource (lib "eagle-import") (part "LM3671MFX-ADJ_NOPB"))
    )
    (comp (ref "U11-S")
      (value "SN74LV1T34")
      (footprint "eagle-import:SOT65P210X110-5")
      (libsource (lib "eagle-import") (part "SN74LV1T34"))
    )
    (comp (ref "U12-S")
      (value "SN74LV1T34")
      (footprint "eagle-import:SOT65P210X110-5")
      (libsource (lib "eagle-import") (part "SN74LV1T34"))
    )
    (comp (ref "U13-S")
      (value "SN74LV1T34")
      (footprint "eagle-import:SOT65P210X110-5")
      (libsource (lib "eagle-import") (part "SN74LV1T34"))
    )
    (comp (ref "U14-S")
      (value "SN74LV1T34")
      (footprint "eagle-import:SOT65P210X110-5")
      (libsource (lib "eagle-import") (part "SN74LV1T34"))
    )
    (comp (ref "VR1-LS1C")
      (value "TRIM_US-LI10")
      (footprint "eagle-import:LI10")
      (libsource (lib "eagle-import") (part "TRIM_US-LI10"))
    )
    (comp (ref "Y1-C")
      (value "NX3225GD-8MHZ-STD-CRA-3")
      (footprint "eagle-import:3.2X2.5_KX-7")
      (libsource (lib "eagle-import") (part "KX-7"))
    )
  )
  (nets
    (net (code "13") (name "/EX_ANT") (class "Default")
      (node (ref "AT1-S") (pin "1") (pinfunction "SIGNAL_1") (pintype "bidirectional"))
      (node (ref "U4-S") (pin "11") (pinfunction "EX_ANT_11") (pintype "bidirectional"))
    )
    (net (code "14") (name "/SENSOR_ERROR") (class "Default")
      (node (ref "J3-CS") (pin "2") (pinfunction "2_2") (pintype "passive"))
    )
    (net (code "15") (name "/SENSOR_NOMINAL") (class "Default")
      (node (ref "J3-CS") (pin "1") (pinfunction "1_1") (pintype "passive"))
    )
    (net (code "22") (name "1V8") (class "Default")
      (node (ref "C2-0S") (pin "1") (pinfunction "1_1") (pintype "passive"))
      (node (ref "C2-1S") (pin "1") (pinfunction "1_1") (pintype "passive"))
      (node (ref "C3-1S") (pin "1") (pinfunction "1_1") (pintype "passive"))
      (node (ref "D1-1S") (pin "A") (pinfunction "A_A") (pintype "passive"))
      (node (ref "L1-0S") (pin "P$2") (pinfunction "2_P$2") (pintype "passive"))
      (node (ref "U0-S") (pin "4") (pinfunction "FB_4") (pintype "bidirectional"))
      (node (ref "U1-S") (pin "13") (pinfunction "VDD_13") (pintype "bidirectional"))
      (node (ref "U1-S") (pin "8") (pinfunction "VDDIO_8") (pintype "bidirectional"))
      (node (ref "U12-S") (pin "5") (pinfunction "VCC_5") (pintype "bidirectional"))
      (node (ref "U13-S") (pin "5") (pinfunction "VCC_5") (pintype "bidirectional"))
      (node (ref "U14-S") (pin "5") (pinfunction "VCC_5") (pintype "bidirectional"))
    )
    (net (code "23") (name "3D-FIX") (class "Default")
      (node (ref "D3-4S") (pin "A") (pinfunction "A_A") (pintype "passive"))
      (node (ref "U4-S") (pin "5") (pinfunction "3D-FIX_5") (pintype "bidirectional"))
    )
    (net (code "24") (name "3V3") (class "Default")
      (node (ref "C1-0C") (pin "1") (pinfunction "1_1") (pintype "passive"))
      (node (ref "C1-0S") (pin "1") (pinfunction "1_1") (pintype "passive"))
      (node (ref "C1-2C") (pin "1") (pinfunction "1_1") (pintype "passive"))
      (node (ref "C1-3S") (pin "1") (pinfunction "1_1") (pintype "passive"))
      (node (ref "C1-9P") (pin "1") (pinfunction "1_1") (pintype "passive"))
      (node (ref "C1-C") (pin "1") (pinfunction "1_1") (pintype "passive"))
      (node (ref "C10-0C") (pin "1") (pinfunction "1_1") (pintype "passive"))
      (node (ref "C11-0C") (pin "1") (pinfunction "1_1") (pintype "passive"))
      (node (ref "C12-0C") (pin "1") (pinfunction "1_1") (pintype "passive"))
      (node (ref "C13-0C") (pin "1") (pinfunction "1_1") (pintype "passive"))
      (node (ref "C14-0C") (pin "1") (pinfunction "1_1") (pintype "passive"))
      (node (ref "C2-0C") (pin "1") (pinfunction "1_1") (pintype "passive"))
      (node (ref "C3-0C") (pin "1") (pinfunction "1_1") (pintype "passive"))
      (node (ref "C4-0C") (pin "1") (pinfunction "1_1") (pintype "passive"))
      (node (ref "C4-9P") (pin "1") (pinfunction "1_1") (pintype "passive"))
      (node (ref "C5-0C") (pin "1") (pinfunction "1_1") (pintype "passive"))
      (node (ref "C6-0C") (pin "1") (pinfunction "1_1") (pintype "passive"))
      (node (ref "C7-0C") (pin "1") (pinfunction "1_1") (pintype "passive"))
      (node (ref "C8-0C") (pin "1") (pinfunction "1_1") (pintype "passive"))
      (node (ref "C9-0C") (pin "1") (pinfunction "1_1") (pintype "passive"))
      (node (ref "D1-2S") (pin "A") (pinfunction "A_A") (pintype "passive"))
      (node (ref "D1-3S") (pin "A") (pinfunction "A_A") (pintype "passive"))
      (node (ref "D1-4S") (pin "A") (pinfunction "A_A") (pintype "passive"))
      (node (ref "FB1-0C") (pin "1") (pinfunction "1_1") (pintype "bidirectional"))
      (node (ref "J1-C") (pin "4") (pinfunction "4_4") (pintype "passive"))
      (node (ref "JP-CP") (pin "1") (pinfunction "1_1") (pintype "passive"))
      (node (ref "JP-CS") (pin "1") (pinfunction "1_1") (pintype "passive"))
      (node (ref "L1-9P") (pin "2") (pinfunction "2_2") (pintype "bidirectional"))
      (node (ref "R1-2C") (pin "1") (pinfunction "1_1") (pintype "passive"))
      (node (ref "R1-9P") (pin "2") (pinfunction "2_2") (pintype "passive"))
      (node (ref "R2-2C") (pin "1") (pinfunction "1_1") (pintype "passive"))
      (node (ref "R3-9P") (pin "2") (pinfunction "2_2") (pintype "passive"))
      (node (ref "R3-J2C") (pin "2") (pinfunction "2_2") (pintype "passive"))
      (node (ref "R4-2C") (pin "1") (pinfunction "1_1") (pintype "passive"))
      (node (ref "S0-0C") (pin "1") (pinfunction "S_1") (pintype "passive"))
      (node (ref "U0-C") (pin "108") (pinfunction "VDD_9_108") (pintype "power_in"))
      (node (ref "U0-C") (pin "121") (pinfunction "VDD_10_121") (pintype "power_in"))
      (node (ref "U0-C") (pin "131") (pinfunction "VDD_11_131") (pintype "power_in"))
      (node (ref "U0-C") (pin "143") (pinfunction "PDR_ON_143") (pintype "bidirectional"))
      (node (ref "U0-C") (pin "144") (pinfunction "VDD_12_144") (pintype "power_in"))
      (node (ref "U0-C") (pin "17") (pinfunction "VDD_1_17") (pintype "power_in"))
      (node (ref "U0-C") (pin "30") (pinfunction "VDD_2_30") (pintype "power_in"))
      (node (ref "U0-C") (pin "39") (pinfunction "VDD_3_39") (pintype "power_in"))
      (node (ref "U0-C") (pin "52") (pinfunction "VDD_4_52") (pintype "power_in"))
      (node (ref "U0-C") (pin "6") (pinfunction "VBAT_6") (pintype "bidirectional"))
      (node (ref "U0-C") (pin "62") (pinfunction "VDD_5_62") (pintype "power_in"))
      (node (ref "U0-C") (pin "72") (pinfunction "VDD_6_72") (pintype "power_in"))
      (node (ref "U0-C") (pin "84") (pinfunction "VDD_7_84") (pintype "power_in"))
      (node (ref "U0-C") (pin "95") (pinfunction "VDD_8_95") (pintype "power_in"))
      (node (ref "U0-S") (pin "1") (pinfunction "VI_1") (pintype "bidirectional"))
      (node (ref "U0-S") (pin "3") (pinfunction "EN_3") (pintype "bidirectional"))
      (node (ref "U1-C") (pin "7") (pinfunction "VCC_7") (pintype "bidirectional"))
      (node (ref "U11-S") (pin "5") (pinfunction "VCC_5") (pintype "bidirectional"))
      (node (ref "U2-C") (pin "8") (pinfunction "VDD_8") (pintype "bidirectional"))
      (node (ref "U3-S") (pin "P$1") (pinfunction "VDD_P$1") (pintype "bidirectional"))
      (node (ref "U4-S") (pin "1") (pinfunction "VCC_1") (pintype "bidirectional"))
      (node (ref "U7-P") (pin "8") (pinfunction "VCC_8") (pintype "bidirectional"))
      (node (ref "U8-P") (pin "8") (pinfunction "VCC_8") (pintype "bidirectional"))
    )
    (net (code "25") (name "5V") (class "Default")
      (node (ref "C2-2S") (pin "1") (pinfunction "1_1") (pintype "passive"))
      (node (ref "C3-2P") (pin "1") (pinfunction "1_1") (pintype "passive"))
      (node (ref "C3-9P") (pin "1") (pinfunction "1_1") (pintype "passive"))
      (node (ref "C4-2P") (pin "1") (pinfunction "1_1") (pintype "passive"))
      (node (ref "C5-2P") (pin "1") (pinfunction "1_1") (pintype "passive"))
      (node (ref "J1-9P") (pin "14") (pinfunction "14_14") (pintype "passive"))
      (node (ref "JP-CP") (pin "2") (pinfunction "2_2") (pintype "passive"))
      (node (ref "JP-CS") (pin "2") (pinfunction "2_2") (pintype "passive"))
      (node (ref "R1-2P") (pin "2") (pinfunction "2_2") (pintype "passive"))
      (node (ref "U2-P") (pin "17") (pinfunction "VOUT_1_17") (pintype "bidirectional"))
      (node (ref "U2-P") (pin "18") (pinfunction "VOUT_2_18") (pintype "bidirectional"))
      (node (ref "U2-P") (pin "19") (pinfunction "VOUT_3_19") (pintype "bidirectional"))
      (node (ref "U2-P") (pin "20") (pinfunction "VOUT_4_20") (pintype "bidirectional"))
      (node (ref "U2-S") (pin "8") (pinfunction "VDD_8") (pintype "bidirectional"))
      (node (ref "U9-P") (pin "1") (pinfunction "VIN_1") (pintype "bidirectional"))
      (node (ref "U9-P") (pin "3") (pinfunction "EN_3") (pintype "bidirectional"))
      (node (ref "VR1-LS1C") (pin "A") (pinfunction "A_A") (pintype "passive"))
    )
    (net (code "26") (name "ACCEL_ANALOG") (class "Default")
      (node (ref "C1-2S") (pin "1") (pinfunction "1_1") (pintype "passive"))
      (node (ref "JP-CS") (pin "5") (pinfunction "5_5") (pintype "passive"))
      (node (ref "R3-2S") (pin "2") (pinfunction "2_2") (pintype "passive"))
      (node (ref "U0-C") (pin "46") (pinfunction "PB0_46") (pintype "bidirectional"))
    )
    (net (code "27") (name "ADC-ERROR") (class "Default")
      (node (ref "D6-C") (pin "A") (pinfunction "A_A") (pintype "passive"))
      (node (ref "U0-C") (pin "59") (pinfunction "PE8_59") (pintype "bidirectional"))
    )
    (net (code "28") (name "ADC_ALERT") (class "Default")
      (node (ref "R4-2C") (pin "2") (pinfunction "2_2") (pintype "passive"))
      (node (ref "U0-C") (pin "98") (pinfunction "PC8_98") (pintype "bidirectional"))
      (node (ref "U2-C") (pin "2") (pinfunction "ALERT/RDY_2") (pintype "bidirectional"))
    )
    (net (code "29") (name "ARMED-LED") (class "Default")
      (node (ref "D0A-C") (pin "A") (pinfunction "A_A") (pintype "passive"))
      (node (ref "D0B-C") (pin "A") (pinfunction "A_A") (pintype "passive"))
      (node (ref "D0C-C") (pin "A") (pinfunction "A_A") (pintype "passive"))
      (node (ref "U0-C") (pin "53") (pinfunction "PF13_53") (pintype "bidirectional"))
    )
    (net (code "30") (name "BATT_MEAS") (class "Default")
      (node (ref "JP-CP") (pin "5") (pinfunction "5_5") (pintype "passive"))
      (node (ref "R3-11P") (pin "1") (pinfunction "1_1") (pintype "passive"))
      (node (ref "R4-11P") (pin "2") (pinfunction "2_2") (pintype "passive"))
      (node (ref "U0-C") (pin "47") (pinfunction "PB1_47") (pintype "bidirectional"))
    )
    (net (code "31") (name "BUZZER_OUT") (class "Default")
      (node (ref "R1-LS1C") (pin "1") (pinfunction "1_1") (pintype "passive"))
      (node (ref "U0-C") (pin "1") (pinfunction "PE2_1") (pintype "bidirectional"))
    )
    (net (code "32") (name "CENTRAL-ERROR") (class "Default")
      (node (ref "D2A-C") (pin "A") (pinfunction "A_A") (pintype "passive"))
      (node (ref "D2B-C") (pin "A") (pinfunction "A_A") (pintype "passive"))
      (node (ref "U0-C") (pin "55") (pinfunction "PF15_55") (pintype "bidirectional"))
    )
    (net (code "33") (name "CENTRAL-NOMINAL") (class "Default")
      (node (ref "D1A-C") (pin "A") (pinfunction "A_A") (pintype "passive"))
      (node (ref "D1B-C") (pin "A") (pinfunction "A_A") (pintype "passive"))
      (node (ref "U0-C") (pin "54") (pinfunction "PF14_54") (pintype "bidirectional"))
    )
    (net (code "34") (name "CLK-1") (class "Default")
      (node (ref "J2-CS") (pin "1") (pinfunction "1_1") (pintype "passive"))
      (node (ref "U0-C") (pin "41") (pinfunction "PA5_41") (pintype "bidirectional"))
      (node (ref "U13-S") (pin "2") (pinfunction "A_2") (pintype "bidirectional"))
      (node (ref "U3-S") (pin "P$8") (pinfunction "SCLK_P$8") (pintype "bidirectional"))
    )
    (net (code "35") (name "CLK-1V8") (class "Default")
      (node (ref "U1-S") (pin "23") (pinfunction "SCL/SCLK_23") (pintype "bidirectional"))
      (node (ref "U13-S") (pin "4") (pinfunction "Y_4") (pintype "bidirectional"))
    )
    (net (code "36") (name "CLK-3") (class "Default")
      (node (ref "U0-C") (pin "111") (pinfunction "PC10_111") (pintype "bidirectional"))
      (node (ref "U1-C") (pin "6") (pinfunction "SCK_6") (pintype "bidirectional"))
    )
    (net (code "37") (name "CMP_LDO_IN") (class "Default")
      (node (ref "R1-11P") (pin "1") (pinfunction "1_1") (pintype "passive"))
      (node (ref "R2-11P") (pin "2") (pinfunction "2_2") (pintype "passive"))
      (node (ref "U7-P") (pin "3") (pinfunction "1IN+_3") (pintype "bidirectional"))
      (node (ref "U7-P") (pin "5") (pinfunction "2IN+_5") (pintype "bidirectional"))
      (node (ref "U8-P") (pin "3") (pinfunction "1IN+_3") (pintype "bidirectional"))
      (node (ref "U8-P") (pin "5") (pinfunction "2IN+_5") (pintype "bidirectional"))
    )
    (net (code "38") (name "CMP_LDO_OUT_1") (class "Default")
      (node (ref "Q1-5P") (pin "2") (pinfunction "G1_2") (pintype "bidirectional"))
      (node (ref "R2-5P") (pin "2") (pinfunction "2_2") (pintype "passive"))
      (node (ref "U7-P") (pin "1") (pinfunction "1OUT_1") (pintype "bidirectional"))
    )
    (net (code "39") (name "CMP_LDO_OUT_2") (class "Default")
      (node (ref "Q1-5P") (pin "4") (pinfunction "G2_4") (pintype "bidirectional"))
      (node (ref "R6-5P") (pin "2") (pinfunction "2_2") (pintype "passive"))
      (node (ref "U7-P") (pin "7") (pinfunction "2OUT_7") (pintype "bidirectional"))
    )
    (net (code "40") (name "CMP_LDO_OUT_3") (class "Default")
      (node (ref "Q1-6P") (pin "2") (pinfunction "G1_2") (pintype "bidirectional"))
      (node (ref "R2-6P") (pin "2") (pinfunction "2_2") (pintype "passive"))
      (node (ref "U8-P") (pin "1") (pinfunction "1OUT_1") (pintype "bidirectional"))
    )
    (net (code "41") (name "CMP_LDO_OUT_4") (class "Default")
      (node (ref "Q1-6P") (pin "4") (pinfunction "G2_4") (pintype "bidirectional"))
      (node (ref "R6-6P") (pin "2") (pinfunction "2_2") (pintype "passive"))
      (node (ref "U8-P") (pin "7") (pinfunction "2OUT_7") (pintype "bidirectional"))
    )
    (net (code "42") (name "CMP_RAIL") (class "Default")
      (node (ref "R3-9P") (pin "1") (pinfunction "1_1") (pintype "passive"))
      (node (ref "R4-9P") (pin "2") (pinfunction "2_2") (pintype "passive"))
      (node (ref "U7-P") (pin "2") (pinfunction "1IN-_2") (pintype "bidirectional"))
      (node (ref "U7-P") (pin "6") (pinfunction "2IN-_6") (pintype "bidirectional"))
      (node (ref "U8-P") (pin "2") (pinfunction "1IN-_2") (pintype "bidirectional"))
      (node (ref "U8-P") (pin "6") (pinfunction "2IN-_6") (pintype "bidirectional"))
    )
    (net (code "43") (name "CS-3") (class "Default")
      (node (ref "U0-C") (pin "114") (pinfunction "PD0_114") (pintype "bidirectional"))
      (node (ref "U1-C") (pin "1") (pinfunction "~{CS}_1") (pintype "bidirectional"))
    )
    (net (code "44") (name "CS1") (class "Default")
      (node (ref "J2-CS") (pin "4") (pinfunction "4_4") (pintype "passive"))
      (node (ref "U0-C") (pin "44") (pinfunction "PC4_44") (pintype "bidirectional"))
      (node (ref "U14-S") (pin "2") (pinfunction "A_2") (pintype "bidirectional"))
    )
    (net (code "45") (name "CS1-1V8") (class "Default")
      (node (ref "U1-S") (pin "22") (pinfunction "NCS_22") (pintype "bidirectional"))
      (node (ref "U14-S") (pin "4") (pinfunction "Y_4") (pintype "bidirectional"))
    )
    (net (code "46") (name "CS2") (class "Default")
      (node (ref "J2-CS") (pin "5") (pinfunction "5_5") (pintype "passive"))
      (node (ref "U0-C") (pin "45") (pinfunction "PC5_45") (pintype "bidirectional"))
      (node (ref "U3-S") (pin "P$4") (pinfunction "CSB_P$4") (pintype "bidirectional"))
      (node (ref "U3-S") (pin "P$5") (pinfunction "CSB_P$5") (pintype "bidirectional"))
    )
    (net (code "48") (name "CTS") (class "Default")
      (node (ref "J1-9P") (pin "13") (pinfunction "13_13") (pintype "passive"))
      (node (ref "J1-CP") (pin "4") (pinfunction "4_4") (pintype "passive"))
      (node (ref "U0-C") (pin "34") (pinfunction "PA0_34") (pintype "bidirectional"))
    )
    (net (code "49") (name "D+") (class "Default")
      (node (ref "R2-J2C") (pin "2") (pinfunction "2_2") (pintype "passive"))
      (node (ref "R3-J2C") (pin "1") (pinfunction "1_1") (pintype "passive"))
      (node (ref "U0-C") (pin "104") (pinfunction "PA12_104") (pintype "bidirectional"))
    )
    (net (code "50") (name "D-") (class "Default")
      (node (ref "R1-J2C") (pin "2") (pinfunction "2_2") (pintype "passive"))
      (node (ref "U0-C") (pin "103") (pinfunction "PA11_103") (pintype "bidirectional"))
    )
    (net (code "51") (name "DISARM_INPUT") (class "Default")
      (node (ref "R0-0C") (pin "2") (pinfunction "2_2") (pintype "passive"))
      (node (ref "S0-0C") (pin "3") (pinfunction "P_3") (pintype "passive"))
      (node (ref "U0-C") (pin "89") (pinfunction "PG4_89") (pintype "bidirectional"))
    )
    (net (code "52") (name "DROGUE-LED") (class "Default")
      (node (ref "D3-C") (pin "A") (pinfunction "A_A") (pintype "passive"))
      (node (ref "U0-C") (pin "56") (pinfunction "PG0_56") (pintype "bidirectional"))
    )
    (net (code "53") (name "FET_A") (class "Default")
      (node (ref "J2-P") (pin "2") (pinfunction "2_2") (pintype "bidirectional"))
      (node (ref "Q1-5P") (pin "7") (pinfunction "D1_1_7") (pintype "bidirectional"))
      (node (ref "Q1-5P") (pin "8") (pinfunction "D1_2_8") (pintype "bidirectional"))
      (node (ref "R3-5P") (pin "1") (pinfunction "1_1") (pintype "passive"))
    )
    (net (code "54") (name "FET_B") (class "Default")
      (node (ref "J2-P") (pin "4") (pinfunction "4_4") (pintype "bidirectional"))
      (node (ref "Q1-5P") (pin "5") (pinfunction "D2_1_5") (pintype "bidirectional"))
      (node (ref "Q1-5P") (pin "6") (pinfunction "D2_2_6") (pintype "bidirectional"))
      (node (ref "R7-5P") (pin "1") (pinfunction "1_1") (pintype "passive"))
    )
    (net (code "55") (name "FET_C") (class "Default")
      (node (ref "J2-P") (pin "6") (pinfunction "6_6") (pintype "bidirectional"))
      (node (ref "Q1-6P") (pin "7") (pinfunction "D1_1_7") (pintype "bidirectional"))
      (node (ref "Q1-6P") (pin "8") (pinfunction "D1_2_8") (pintype "bidirectional"))
      (node (ref "R3-6P") (pin "1") (pinfunction "1_1") (pintype "passive"))
    )
    (net (code "56") (name "FET_D") (class "Default")
      (node (ref "J2-P") (pin "8") (pinfunction "8_8") (pintype "bidirectional"))
      (node (ref "Q1-6P") (pin "5") (pinfunction "D2_1_5") (pintype "bidirectional"))
      (node (ref "Q1-6P") (pin "6") (pinfunction "D2_2_6") (pintype "bidirectional"))
      (node (ref "R7-6P") (pin "1") (pinfunction "1_1") (pintype "passive"))
    )
    (net (code "57") (name "FIRE_A") (class "Default")
      (node (ref "J2-CP") (pin "1") (pinfunction "1_1") (pintype "passive"))
      (node (ref "R1-5P") (pin "2") (pinfunction "2_2") (pintype "passive"))
      (node (ref "R2-5P") (pin "1") (pinfunction "1_1") (pintype "passive"))
      (node (ref "U0-C") (pin "11") (pinfunction "PF1_11") (pintype "bidirectional"))
    )
    (net (code "58") (name "FIRE_B") (class "Default")
      (node (ref "J2-CP") (pin "2") (pinfunction "2_2") (pintype "passive"))
      (node (ref "R5-5P") (pin "2") (pinfunction "2_2") (pintype "passive"))
      (node (ref "R6-5P") (pin "1") (pinfunction "1_1") (pintype "passive"))
      (node (ref "U0-C") (pin "12") (pinfunction "PF2_12") (pintype "bidirectional"))
    )
    (net (code "59") (name "FIRE_C") (class "Default")
      (node (ref "J2-CP") (pin "3") (pinfunction "3_3") (pintype "passive"))
      (node (ref "R1-6P") (pin "2") (pinfunction "2_2") (pintype "passive"))
      (node (ref "R2-6P") (pin "1") (pinfunction "1_1") (pintype "passive"))
      (node (ref "U0-C") (pin "13") (pinfunction "PF3_13") (pintype "bidirectional"))
    )
    (net (code "60") (name "FIRE_D") (class "Default")
      (node (ref "J2-CP") (pin "4") (pinfunction "4_4") (pintype "passive"))
      (node (ref "R5-6P") (pin "2") (pinfunction "2_2") (pintype "passive"))
      (node (ref "R6-6P") (pin "1") (pinfunction "1_1") (pintype "passive"))
      (node (ref "U0-C") (pin "14") (pinfunction "PF4_14") (pintype "bidirectional"))
    )
    (net (code "61") (name "GND") (class "Default")
      (node (ref "1S_LIPO") (pin "2") (pinfunction "2_2") (pintype "bidirectional"))
      (node (ref "AT1-S") (pin "2") (pinfunction "GND_1_2") (pintype "bidirectional"))
      (node (ref "AT1-S") (pin "3") (pinfunction "GND_2_3") (pintype "bidirectional"))
      (node (ref "AT1-S") (pin "4") (pinfunction "GND_3_4") (pintype "bidirectional"))
      (node (ref "C1") (pin "2") (pinfunction "2_2") (pintype "passive"))
      (node (ref "C1-0C") (pin "2") (pinfunction "2_2") (pintype "passive"))
      (node (ref "C1-0S") (pin "2") (pinfunction "2_2") (pintype "passive"))
      (node (ref "C1-11P") (pin "2") (pinfunction "2_2") (pintype "passive"))
      (node (ref "C1-1P") (pin "2") (pinfunction "2_2") (pintype "passive"))
      (node (ref "C1-1S") (pin "2") (pinfunction "2_2") (pintype "passive"))
      (node (ref "C1-2C") (pin "2") (pinfunction "2_2") (pintype "passive"))
      (node (ref "C1-2P") (pin "2") (pinfunction "2_2") (pintype "passive"))
      (node (ref "C1-2S") (pin "2") (pinfunction "2_2") (pintype "passive"))
      (node (ref "C1-3S") (pin "2") (pinfunction "2_2") (pintype "passive"))
      (node (ref "C1-C") (pin "2") (pinfunction "2_2") (pintype "passive"))
      (node (ref "C10-0C") (pin "2") (pinfunction "2_2") (pintype "passive"))
      (node (ref "C11-0C") (pin "2") (pinfunction "2_2") (pintype "passive"))
      (node (ref "C12-0C") (pin "2") (pinfunction "2_2") (pintype "passive"))
      (node (ref "C13-0C") (pin "2") (pinfunction "2_2") (pintype "passive"))
      (node (ref "C14-0C") (pin "2") (pinfunction "2_2") (pintype "passive"))
      (node (ref "C15-0C") (pin "2") (pinfunction "2_2") (pintype "passive"))
      (node (ref "C16-0C") (pin "2") (pinfunction "2_2") (pintype "passive"))
      (node (ref "C17-0C") (pin "2") (pinfunction "2_2") (pintype "passive"))
      (node (ref "C2") (pin "2") (pinfunction "2_2") (pintype "passive"))
      (node (ref "C2-0C") (pin "2") (pinfunction "2_2") (pintype "passive"))
      (node (ref "C2-0S") (pin "2") (pinfunction "2_2") (pintype "passive"))
      (node (ref "C2-1P") (pin "2") (pinfunction "2_2") (pintype "passive"))
      (node (ref "C2-1S") (pin "2") (pinfunction "2_2") (pintype "passive"))
      (node (ref "C2-2P") (pin "2") (pinfunction "2_2") (pintype "passive"))
      (node (ref "C2-2S") (pin "2") (pinfunction "2_2") (pintype "passive"))
      (node (ref "C2-9P") (pin "2") (pinfunction "2_2") (pintype "passive"))
      (node (ref "C3-0C") (pin "2") (pinfunction "2_2") (pintype "passive"))
      (node (ref "C3-1S") (pin "2") (pinfunction "2_2") (pintype "passive"))
      (node (ref "C3-9P") (pin "2") (pinfunction "2_2") (pintype "passive"))
      (node (ref "C4-0C") (pin "2") (pinfunction "2_2") (pintype "passive"))
      (node (ref "C4-2P") (pin "2") (pinfunction "2_2") (pintype "passive"))
      (node (ref "C4-9P") (pin "2") (pinfunction "2_2") (pintype "passive"))
      (node (ref "C5-0C") (pin "2") (pinfunction "2_2") (pintype "passive"))
      (node (ref "C5-2P") (pin "2") (pinfunction "2_2") (pintype "passive"))
      (node (ref "C6-0C") (pin "2") (pinfunction "2_2") (pintype "passive"))
      (node (ref "C7-0C") (pin "2") (pinfunction "2_2") (pintype "passive"))
      (node (ref "C8-0C") (pin "2") (pinfunction "2_2") (pintype "passive"))
      (node (ref "C9-0C") (pin "2") (pinfunction "2_2") (pintype "passive"))
      (node (ref "J1-9P") (pin "15") (pinfunction "15_15") (pintype "passive"))
      (node (ref "J1-C") (pin "1") (pinfunction "1_1") (pintype "passive"))
      (node (ref "J2-C") (pin "5") (pinfunction "GND_5") (pintype "power_in"))
      (node (ref "J2-C") (pin "S1") (pinfunction "SHIELD_S1") (pintype "power_in"))
      (node (ref "J2-C") (pin "S2") (pinfunction "SHIELD_S2") (pintype "power_in"))
      (node (ref "J2-C") (pin "S3") (pinfunction "SHIELD_S3") (pintype "power_in"))
      (node (ref "J2-C") (pin "S4") (pinfunction "SHIELD_S4") (pintype "power_in"))
      (node (ref "JP-CP") (pin "3") (pinfunction "3_3") (pintype "passive"))
      (node (ref "JP-CS") (pin "3") (pinfunction "3_3") (pintype "passive"))
      (node (ref "LS1-C") (pin "V-") (pinfunction "V-_V-") (pintype "bidirectional"))
      (node (ref "Q1-5P") (pin "1") (pinfunction "S1_1") (pintype "bidirectional"))
      (node (ref "Q1-5P") (pin "3") (pinfunction "S2_3") (pintype "bidirectional"))
      (node (ref "Q1-6P") (pin "1") (pinfunction "S1_1") (pintype "bidirectional"))
      (node (ref "Q1-6P") (pin "3") (pinfunction "S2_3") (pintype "bidirectional"))
      (node (ref "R0-0C") (pin "1") (pinfunction "1_1") (pintype "passive"))
      (node (ref "R0A-C") (pin "2") (pinfunction "2_2") (pintype "passive"))
      (node (ref "R0B-C") (pin "2") (pinfunction "2_2") (pintype "passive"))
      (node (ref "R0C-C") (pin "2") (pinfunction "2_2") (pintype "passive"))
      (node (ref "R1-0C") (pin "2") (pinfunction "2_2") (pintype "passive"))
      (node (ref "R1-1S") (pin "2") (pinfunction "2_2") (pintype "passive"))
      (node (ref "R1-2S") (pin "2") (pinfunction "2_2") (pintype "passive"))
      (node (ref "R1-3S") (pin "2") (pinfunction "2_2") (pintype "passive"))
      (node (ref "R1-4S") (pin "2") (pinfunction "2_2") (pintype "passive"))
      (node (ref "R1-5P") (pin "1") (pinfunction "1_1") (pintype "passive"))
      (node (ref "R1-6P") (pin "1") (pinfunction "1_1") (pintype "passive"))
      (node (ref "R1A-C") (pin "2") (pinfunction "2_2") (pintype "passive"))
      (node (ref "R1A-S") (pin "2") (pinfunction "2_2") (pintype "passive"))
      (node (ref "R1B-C") (pin "2") (pinfunction "2_2") (pintype "passive"))
      (node (ref "R1B-S") (pin "2") (pinfunction "2_2") (pintype "passive"))
      (node (ref "R2-11P") (pin "1") (pinfunction "1_1") (pintype "passive"))
      (node (ref "R2-1P") (pin "1") (pinfunction "1_1") (pintype "passive"))
      (node (ref "R2-1S") (pin "2") (pinfunction "2_2") (pintype "passive"))
      (node (ref "R2-2P") (pin "1") (pinfunction "1_1") (pintype "passive"))
      (node (ref "R2-2S") (pin "2") (pinfunction "2_2") (pintype "passive"))
      (node (ref "R2-3S") (pin "2") (pinfunction "2_2") (pintype "passive"))
      (node (ref "R2-4S") (pin "2") (pinfunction "2_2") (pintype "passive"))
      (node (ref "R2-9P") (pin "1") (pinfunction "1_1") (pintype "passive"))
      (node (ref "R2A-C") (pin "2") (pinfunction "2_2") (pintype "passive"))
      (node (ref "R2A-S") (pin "2") (pinfunction "2_2") (pintype "passive"))
      (node (ref "R2B-C") (pin "2") (pinfunction "2_2") (pintype "passive"))
      (node (ref "R2B-S") (pin "2") (pinfunction "2_2") (pintype "passive"))
      (node (ref "R3-11P") (pin "2") (pinfunction "2_2") (pintype "passive"))
      (node (ref "R3-2C") (pin "1") (pinfunction "1_1") (pintype "passive"))
      (node (ref "R3-4S") (pin "2") (pinfunction "2_2") (pintype "passive"))
      (node (ref "R3-C") (pin "2") (pinfunction "2_2") (pintype "passive"))
      (node (ref "R3-LS1C") (pin "1") (pinfunction "1_1") (pintype "passive"))
      (node (ref "R4-5P") (pin "1") (pinfunction "1_1") (pintype "passive"))
      (node (ref "R4-6P") (pin "1") (pinfunction "1_1") (pintype "passive"))
      (node (ref "R4-9P") (pin "1") (pinfunction "1_1") (pintype "passive"))
      (node (ref "R4-C") (pin "2") (pinfunction "2_2") (pintype "passive"))
      (node (ref "R5-5P") (pin "1") (pinfunction "1_1") (pintype "passive"))
      (node (ref "R5-6P") (pin "1") (pinfunction "1_1") (pintype "passive"))
      (node (ref "R5-C") (pin "2") (pinfunction "2_2") (pintype "passive"))
      (node (ref "R6-C") (pin "2") (pinfunction "2_2") (pintype "passive"))
      (node (ref "R8-5P") (pin "1") (pinfunction "1_1") (pintype "passive"))
      (node (ref "R8-6P") (pin "1") (pinfunction "1_1") (pintype "passive"))
      (node (ref "S1-0C") (pin "3") (pinfunction "P_3") (pintype "passive"))
      (node (ref "S1-0C") (pin "4") (pinfunction "P1_4") (pintype "passive"))
      (node (ref "U0-C") (pin "107") (pinfunction "VSS_7_107") (pintype "power_in"))
      (node (ref "U0-C") (pin "120") (pinfunction "VSS_8_120") (pintype "power_in"))
      (node (ref "U0-C") (pin "130") (pinfunction "VSS_9_130") (pintype "power_in"))
      (node (ref "U0-C") (pin "16") (pinfunction "VSS_1_16") (pintype "power_in"))
      (node (ref "U0-C") (pin "31") (pinfunction "VSSA_31") (pintype "power_in"))
      (node (ref "U0-C") (pin "38") (pinfunction "VSS_2_38") (pintype "power_in"))
      (node (ref "U0-C") (pin "51") (pinfunction "VSS_3_51") (pintype "power_in"))
      (node (ref "U0-C") (pin "61") (pinfunction "VSS_4_61") (pintype "power_in"))
      (node (ref "U0-C") (pin "83") (pinfunction "VSS_5_83") (pintype "power_in"))
      (node (ref "U0-C") (pin "94") (pinfunction "VSS_6_94") (pintype "power_in"))
      (node (ref "U0-S") (pin "2") (pinfunction "GND_2") (pintype "bidirectional"))
      (node (ref "U1-C") (pin "8") (pinfunction "VSS_8") (pintype "bidirectional"))
      (node (ref "U1-P") (pin "2") (pinfunction "VSS_2") (pintype "power_in"))
      (node (ref "U1-S") (pin "18") (pinfunction "GND_18") (pintype "bidirectional"))
      (node (ref "U1-S") (pin "20") (pinfunction "RESV.GND_20") (pintype "bidirectional"))
      (node (ref "U11-S") (pin "3") (pinfunction "GND_3") (pintype "bidirectional"))
      (node (ref "U12-S") (pin "3") (pinfunction "GND_3") (pintype "bidirectional"))
      (node (ref "U13-S") (pin "3") (pinfunction "GND_3") (pintype "bidirectional"))
      (node (ref "U14-S") (pin "3") (pinfunction "GND_3") (pintype "bidirectional"))
      (node (ref "U2-C") (pin "3") (pinfunction "GND_3") (pintype "bidirectional"))
      (node (ref "U2-P") (pin "12") (pinfunction "MODE_12") (pintype "bidirectional"))
      (node (ref "U2-P") (pin "13") (pinfunction "SGND_1_13") (pintype "bidirectional"))
      (node (ref "U2-P") (pin "3") (pinfunction "PGND_3") (pintype "bidirectional"))
      (node (ref "U2-S") (pin "7") (pinfunction "VSS_7") (pintype "bidirectional"))
      (node (ref "U3-S") (pin "P$2") (pinfunction "PS_P$2") (pintype "bidirectional"))
      (node (ref "U3-S") (pin "P$3") (pinfunction "GND_P$3") (pintype "bidirectional"))
      (node (ref "U4-S") (pin "12") (pinfunction "GND_12") (pintype "bidirectional"))
      (node (ref "U4-S") (pin "19") (pinfunction "GND_19") (pintype "bidirectional"))
      (node (ref "U4-S") (pin "3") (pinfunction "GND_3") (pintype "bidirectional"))
      (node (ref "U4-S") (pin "8") (pinfunction "GND_8") (pintype "bidirectional"))
      (node (ref "U7-P") (pin "4") (pinfunction "GND_4") (pintype "bidirectional"))
      (node (ref "U8-P") (pin "4") (pinfunction "GND_4") (pintype "bidirectional"))
      (node (ref "U9-P") (pin "2") (pinfunction "GND_2") (pintype "bidirectional"))
    )
    (net (code "62") (name "HOLD") (class "Default")
      (node (ref "U0-C") (pin "77") (pinfunction "PD8_77") (pintype "bidirectional"))
      (node (ref "U1-C") (pin "5") (pinfunction "~{HOLD}/IO3_5") (pintype "bidirectional"))
    )
    (net (code "63") (name "ID") (class "Default")
      (node (ref "J2-C") (pin "4") (pinfunction "ID_4") (pintype "bidirectional"))
      (node (ref "U0-C") (pin "102") (pinfunction "PA10_102") (pintype "bidirectional"))
    )
    (net (code "64") (name "MAIN-LED") (class "Default")
      (node (ref "D4-C") (pin "A") (pinfunction "A_A") (pintype "passive"))
      (node (ref "U0-C") (pin "57") (pinfunction "PG1_57") (pintype "bidirectional"))
    )
    (net (code "65") (name "MASTER_RX-1") (class "Default")
      (node (ref "J1-CS") (pin "1") (pinfunction "1_1") (pintype "passive"))
      (node (ref "U0-C") (pin "97") (pinfunction "PC7_97") (pintype "bidirectional"))
      (node (ref "U4-S") (pin "9") (pinfunction "TX_9") (pintype "bidirectional"))
    )
    (net (code "66") (name "MASTER_RX-2") (class "Default")
      (node (ref "J1-9P") (pin "7") (pinfunction "7_7") (pintype "passive"))
      (node (ref "J1-CP") (pin "2") (pinfunction "2_2") (pintype "passive"))
      (node (ref "U0-C") (pin "37") (pinfunction "PA3_37") (pintype "bidirectional"))
    )
    (net (code "67") (name "MASTER_TX-1") (class "Default")
      (node (ref "J1-CS") (pin "2") (pinfunction "2_2") (pintype "passive"))
      (node (ref "U0-C") (pin "96") (pinfunction "PC6_96") (pintype "bidirectional"))
      (node (ref "U4-S") (pin "10") (pinfunction "RX_10") (pintype "bidirectional"))
    )
    (net (code "68") (name "MASTER_TX-2") (class "Default")
      (node (ref "J1-9P") (pin "9") (pinfunction "9_9") (pintype "passive"))
      (node (ref "J1-CP") (pin "3") (pinfunction "3_3") (pintype "passive"))
      (node (ref "U0-C") (pin "36") (pinfunction "PA2_36") (pintype "bidirectional"))
    )
    (net (code "69") (name "MISO-1") (class "Default")
      (node (ref "J2-CS") (pin "2") (pinfunction "2_2") (pintype "passive"))
      (node (ref "U0-C") (pin "42") (pinfunction "PA6_42") (pintype "bidirectional"))
      (node (ref "U11-S") (pin "4") (pinfunction "Y_4") (pintype "bidirectional"))
    )
    (net (code "70") (name "MISO-1V8") (class "Default")
      (node (ref "U1-S") (pin "9") (pinfunction "SDO/AD0_9") (pintype "bidirectional"))
      (node (ref "U11-S") (pin "2") (pinfunction "A_2") (pintype "bidirectional"))
    )
    (net (code "71") (name "MISO-3") (class "Default")
      (node (ref "U0-C") (pin "112") (pinfunction "PC11_112") (pintype "bidirectional"))
      (node (ref "U1-C") (pin "2") (pinfunction "SO/IO1_2") (pintype "bidirectional"))
    )
    (net (code "72") (name "MOSI-1") (class "Default")
      (node (ref "J2-CS") (pin "3") (pinfunction "3_3") (pintype "passive"))
      (node (ref "U0-C") (pin "43") (pinfunction "PA7_43") (pintype "bidirectional"))
      (node (ref "U12-S") (pin "2") (pinfunction "A_2") (pintype "bidirectional"))
      (node (ref "U3-S") (pin "P$6") (pinfunction "SDO_P$6") (pintype "bidirectional"))
      (node (ref "U3-S") (pin "P$7") (pinfunction "SDI_P$7") (pintype "bidirectional"))
    )
    (net (code "73") (name "MOSI-1V8") (class "Default")
      (node (ref "U1-S") (pin "24") (pinfunction "SDA/SDI_24") (pintype "bidirectional"))
      (node (ref "U12-S") (pin "4") (pinfunction "Y_4") (pintype "bidirectional"))
    )
    (net (code "74") (name "MOSI-3") (class "Default")
      (node (ref "U0-C") (pin "113") (pinfunction "PC12_113") (pintype "bidirectional"))
      (node (ref "U1-C") (pin "4") (pinfunction "SI/IO0_4") (pintype "bidirectional"))
    )
    (net (code "76") (name "NRST") (class "Default")
      (node (ref "C15-0C") (pin "1") (pinfunction "1_1") (pintype "passive"))
      (node (ref "R2-J1C") (pin "2") (pinfunction "2_2") (pintype "passive"))
      (node (ref "S1-0C") (pin "1") (pinfunction "S_1") (pintype "passive"))
      (node (ref "S1-0C") (pin "2") (pinfunction "S1_2") (pintype "passive"))
      (node (ref "U0-C") (pin "25") (pinfunction "NRST_25") (pintype "input"))
    )
    (net (code "77") (name "Net-(D0A-C-PadC)") (class "Default")
      (node (ref "D0A-C") (pin "C") (pinfunction "C_C") (pintype "passive"))
      (node (ref "R0A-C") (pin "1") (pinfunction "1_1") (pintype "passive"))
    )
    (net (code "78") (name "Net-(D0B-C-PadC)") (class "Default")
      (node (ref "D0B-C") (pin "C") (pinfunction "C_C") (pintype "passive"))
      (node (ref "R0B-C") (pin "1") (pinfunction "1_1") (pintype "passive"))
    )
    (net (code "79") (name "Net-(D0C-C-PadC)") (class "Default")
      (node (ref "D0C-C") (pin "C") (pinfunction "C_C") (pintype "passive"))
      (node (ref "R0C-C") (pin "1") (pinfunction "1_1") (pintype "passive"))
    )
    (net (code "80") (name "Net-(D1-1P-PadC)") (class "Default")
      (node (ref "D1-1P") (pin "C") (pinfunction "C_C") (pintype "passive"))
      (node (ref "R1-1P") (pin "1") (pinfunction "1_1") (pintype "passive"))
    )
    (net (code "81") (name "Net-(D1-1S-PadC)") (class "Default")
      (node (ref "D1-1S") (pin "C") (pinfunction "C_C") (pintype "passive"))
      (node (ref "R1-1S") (pin "1") (pinfunction "1_1") (pintype "passive"))
    )
    (net (code "82") (name "Net-(D1-2S-PadC)") (class "Default")
      (node (ref "D1-2S") (pin "C") (pinfunction "C_C") (pintype "passive"))
      (node (ref "R1-2S") (pin "1") (pinfunction "1_1") (pintype "passive"))
    )
    (net (code "83") (name "Net-(D1-3S-PadC)") (class "Default")
      (node (ref "D1-3S") (pin "C") (pinfunction "C_C") (pintype "passive"))
      (node (ref "R1-3S") (pin "1") (pinfunction "1_1") (pintype "passive"))
    )
    (net (code "84") (name "Net-(D1-4S-PadC)") (class "Default")
      (node (ref "D1-4S") (pin "C") (pinfunction "C_C") (pintype "passive"))
      (node (ref "R1-4S") (pin "1") (pinfunction "1_1") (pintype "passive"))
    )
    (net (code "85") (name "Net-(D1-11P-A)") (class "Default")
      (node (ref "D1-11P") (pin "2") (pinfunction "A_2") (pintype "bidirectional"))
      (node (ref "R4-11P") (pin "1") (pinfunction "1_1") (pintype "passive"))
      (node (ref "S1-P") (pin "S") (pinfunction "S_S") (pintype "passive"))
    )
    (net (code "86") (name "Net-(D1A-C-PadC)") (class "Default")
      (node (ref "D1A-C") (pin "C") (pinfunction "C_C") (pintype "passive"))
      (node (ref "R1A-C") (pin "1") (pinfunction "1_1") (pintype "passive"))
    )
    (net (code "87") (name "Net-(D1A-S-PadC)") (class "Default")
      (node (ref "D1A-S") (pin "C") (pinfunction "C_C") (pintype "passive"))
      (node (ref "R1A-S") (pin "1") (pinfunction "1_1") (pintype "passive"))
    )
    (net (code "88") (name "Net-(D1B-C-PadC)") (class "Default")
      (node (ref "D1B-C") (pin "C") (pinfunction "C_C") (pintype "passive"))
      (node (ref "R1B-C") (pin "1") (pinfunction "1_1") (pintype "passive"))
    )
    (net (code "89") (name "Net-(D1B-S-PadC)") (class "Default")
      (node (ref "D1B-S") (pin "C") (pinfunction "C_C") (pintype "passive"))
      (node (ref "R1B-S") (pin "1") (pinfunction "1_1") (pintype "passive"))
    )
    (net (code "90") (name "Net-(D2-1S-PadC)") (class "Default")
      (node (ref "D2-1S") (pin "C") (pinfunction "C_C") (pintype "passive"))
      (node (ref "R2-1S") (pin "1") (pinfunction "1_1") (pintype "passive"))
    )
    (net (code "91") (name "Net-(D2-2S-PadC)") (class "Default")
      (node (ref "D2-2S") (pin "C") (pinfunction "C_C") (pintype "passive"))
      (node (ref "R2-2S") (pin "1") (pinfunction "1_1") (pintype "passive"))
    )
    (net (code "92") (name "Net-(D2-3S-PadC)") (class "Default")
      (node (ref "D2-3S") (pin "C") (pinfunction "C_C") (pintype "passive"))
      (node (ref "R2-3S") (pin "1") (pinfunction "1_1") (pintype "passive"))
    )
    (net (code "93") (name "Net-(D2-4S-PadC)") (class "Default")
      (node (ref "D2-4S") (pin "C") (pinfunction "C_C") (pintype "passive"))
      (node (ref "R2-4S") (pin "1") (pinfunction "1_1") (pintype "passive"))
    )
    (net (code "94") (name "Net-(D2A-C-PadC)") (class "Default")
      (node (ref "D2A-C") (pin "C") (pinfunction "C_C") (pintype "passive"))
      (node (ref "R2A-C") (pin "1") (pinfunction "1_1") (pintype "passive"))
    )
    (net (code "95") (name "Net-(D2A-S-PadC)") (class "Default")
      (node (ref "D2A-S") (pin "C") (pinfunction "C_C") (pintype "passive"))
      (node (ref "R2A-S") (pin "1") (pinfunction "1_1") (pintype "passive"))
    )
    (net (code "96") (name "Net-(D2B-C-PadC)") (class "Default")
      (node (ref "D2B-C") (pin "C") (pinfunction "C_C") (pintype "passive"))
      (node (ref "R2B-C") (pin "1") (pinfunction "1_1") (pintype "passive"))
    )
    (net (code "97") (name "Net-(D2B-S-PadC)") (class "Default")
      (node (ref "D2B-S") (pin "C") (pinfunction "C_C") (pintype "passive"))
      (node (ref "R2B-S") (pin "1") (pinfunction "1_1") (pintype "passive"))
    )
    (net (code "98") (name "Net-(D3-4S-PadC)") (class "Default")
      (node (ref "D3-4S") (pin "C") (pinfunction "C_C") (pintype "passive"))
      (node (ref "R3-4S") (pin "1") (pinfunction "1_1") (pintype "passive"))
    )
    (net (code "99") (name "Net-(D3-C-PadC)") (class "Default")
      (node (ref "D3-C") (pin "C") (pinfunction "C_C") (pintype "passive"))
      (node (ref "R3-C") (pin "1") (pinfunction "1_1") (pintype "passive"))
    )
    (net (code "100") (name "Net-(D4-C-PadC)") (class "Default")
      (node (ref "D4-C") (pin "C") (pinfunction "C_C") (pintype "passive"))
      (node (ref "R4-C") (pin "1") (pinfunction "1_1") (pintype "passive"))
    )
    (net (code "101") (name "Net-(D5-C-PadC)") (class "Default")
      (node (ref "D5-C") (pin "C") (pinfunction "C_C") (pintype "passive"))
      (node (ref "R5-C") (pin "1") (pinfunction "1_1") (pintype "passive"))
    )
    (net (code "102") (name "Net-(D6-C-PadC)") (class "Default")
      (node (ref "D6-C") (pin "C") (pinfunction "C_C") (pintype "passive"))
      (node (ref "R6-C") (pin "1") (pinfunction "1_1") (pintype "passive"))
    )
    (net (code "103") (name "Net-(J1-C-Pad5)") (class "Default")
      (node (ref "J1-C") (pin "5") (pinfunction "5_5") (pintype "passive"))
      (node (ref "R1-J1C") (pin "1") (pinfunction "1_1") (pintype "passive"))
    )
    (net (code "104") (name "Net-(J1-C-Pad6)") (class "Default")
      (node (ref "J1-C") (pin "6") (pinfunction "6_6") (pintype "passive"))
      (node (ref "R2-J1C") (pin "1") (pinfunction "1_1") (pintype "passive"))
    )
    (net (code "105") (name "Net-(J2-C-D+)") (class "Default")
      (node (ref "J2-C") (pin "3") (pinfunction "D+_3") (pintype "bidirectional"))
      (node (ref "R2-J2C") (pin "1") (pinfunction "1_1") (pintype "passive"))
    )
    (net (code "106") (name "Net-(J2-C-D-)") (class "Default")
      (node (ref "J2-C") (pin "2") (pinfunction "D-_2") (pintype "bidirectional"))
      (node (ref "R1-J2C") (pin "1") (pinfunction "1_1") (pintype "passive"))
    )
    (net (code "107") (name "Net-(L1-0S-1)") (class "Default")
      (node (ref "L1-0S") (pin "P$1") (pinfunction "1_P$1") (pintype "passive"))
      (node (ref "U0-S") (pin "5") (pinfunction "SW_5") (pintype "bidirectional"))
    )
    (net (code "108") (name "Net-(LS1-C-PadV+)") (class "Default")
      (node (ref "LS1-C") (pin "V+") (pinfunction "V+_V+") (pintype "bidirectional"))
      (node (ref "R2-LS1C") (pin "1") (pinfunction "1_1") (pintype "passive"))
    )
    (net (code "109") (name "Net-(Q1-LS1C-B)") (class "Default")
      (node (ref "Q1-LS1C") (pin "1") (pinfunction "B_1") (pintype "passive"))
      (node (ref "R1-LS1C") (pin "2") (pinfunction "2_2") (pintype "passive"))
    )
    (net (code "110") (name "Net-(Q1-LS1C-C)") (class "Default")
      (node (ref "Q1-LS1C") (pin "2") (pinfunction "C_2") (pintype "passive"))
      (node (ref "VR1-LS1C") (pin "S") (pinfunction "S_S") (pintype "passive"))
    )
    (net (code "111") (name "Net-(Q1-LS1C-E)") (class "Default")
      (node (ref "Q1-LS1C") (pin "3") (pinfunction "E_3") (pintype "passive"))
      (node (ref "R2-LS1C") (pin "2") (pinfunction "2_2") (pintype "passive"))
    )
    (net (code "112") (name "Net-(R3-LS1C-Pad2)") (class "Default")
      (node (ref "R3-LS1C") (pin "2") (pinfunction "2_2") (pintype "passive"))
      (node (ref "VR1-LS1C") (pin "E") (pinfunction "E_E") (pintype "passive"))
    )
    (net (code "113") (name "Net-(U0-C-BOOT0)") (class "Default")
      (node (ref "R1-0C") (pin "1") (pinfunction "1_1") (pintype "passive"))
      (node (ref "U0-C") (pin "138") (pinfunction "BOOT0_138") (pintype "bidirectional"))
    )
    (net (code "114") (name "Net-(U0-C-VCAP_1)") (class "Default")
      (node (ref "C16-0C") (pin "1") (pinfunction "1_1") (pintype "passive"))
      (node (ref "U0-C") (pin "71") (pinfunction "VCAP_1_71") (pintype "bidirectional"))
    )
    (net (code "115") (name "Net-(U0-C-VCAP_2)") (class "Default")
      (node (ref "C17-0C") (pin "1") (pinfunction "1_1") (pintype "passive"))
      (node (ref "U0-C") (pin "106") (pinfunction "VCAP_2_106") (pintype "bidirectional"))
    )
    (net (code "116") (name "Net-(U1-P-PROG)") (class "Default")
      (node (ref "R2-1P") (pin "2") (pinfunction "2_2") (pintype "passive"))
      (node (ref "U1-P") (pin "5") (pinfunction "PROG_5") (pintype "bidirectional"))
    )
    (net (code "117") (name "Net-(U1-P-STAT)") (class "Default")
      (node (ref "R1-1P") (pin "2") (pinfunction "2_2") (pintype "passive"))
      (node (ref "U1-P") (pin "1") (pinfunction "STAT_1") (pintype "bidirectional"))
    )
    (net (code "118") (name "Net-(U1-S-REGOUT)") (class "Default")
      (node (ref "C1-1S") (pin "1") (pinfunction "1_1") (pintype "passive"))
      (node (ref "U1-S") (pin "10") (pinfunction "REGOUT_10") (pintype "bidirectional"))
    )
    (net (code "119") (name "Net-(U2-C-ADDR)") (class "Default")
      (node (ref "R3-2C") (pin "2") (pinfunction "2_2") (pintype "passive"))
      (node (ref "U2-C") (pin "1") (pinfunction "ADDR_1") (pintype "bidirectional"))
    )
    (net (code "120") (name "Net-(U2-P-LX1_1)") (class "Default")
      (node (ref "L1-2P") (pin "2") (pinfunction "2_2") (pintype "bidirectional"))
      (node (ref "U2-P") (pin "4") (pinfunction "LX1_1_4") (pintype "bidirectional"))
    )
    (net (code "121") (name "Net-(U2-P-LX2_1)") (class "Default")
      (node (ref "L1-2P") (pin "1") (pinfunction "1_1") (pintype "bidirectional"))
      (node (ref "U2-P") (pin "1") (pinfunction "LX2_1_1") (pintype "bidirectional"))
    )
    (net (code "122") (name "Net-(U2-S-VOUT)") (class "Default")
      (node (ref "R3-2S") (pin "1") (pinfunction "1_1") (pintype "passive"))
      (node (ref "U2-S") (pin "5") (pinfunction "VOUT_5") (pintype "bidirectional"))
    )
    (net (code "123") (name "OSC_IN") (class "Default")
      (node (ref "C1") (pin "1") (pinfunction "1_1") (pintype "passive"))
      (node (ref "U0-C") (pin "23") (pinfunction "PH0_23") (pintype "bidirectional"))
      (node (ref "Y1-C") (pin "3") (pinfunction "2_3") (pintype "passive"))
    )
    (net (code "124") (name "OSC_OUT") (class "Default")
      (node (ref "C2") (pin "1") (pinfunction "1_1") (pintype "passive"))
      (node (ref "U0-C") (pin "24") (pinfunction "PH1_24") (pintype "bidirectional"))
      (node (ref "Y1-C") (pin "1") (pinfunction "1_1") (pintype "passive"))
    )
    (net (code "125") (name "RTS") (class "Default")
      (node (ref "J1-9P") (pin "5") (pinfunction "5_5") (pintype "passive"))
      (node (ref "J1-CP") (pin "1") (pinfunction "1_1") (pintype "passive"))
      (node (ref "U0-C") (pin "35") (pinfunction "PA1_35") (pintype "bidirectional"))
    )
    (net (code "126") (name "SCL-1") (class "Default")
      (node (ref "R2-2C") (pin "2") (pinfunction "2_2") (pintype "passive"))
      (node (ref "U0-C") (pin "100") (pinfunction "PA8_100") (pintype "bidirectional"))
      (node (ref "U2-C") (pin "10") (pinfunction "SCL_10") (pintype "bidirectional"))
    )
    (net (code "127") (name "SDA-1") (class "Default")
      (node (ref "R1-2C") (pin "2") (pinfunction "2_2") (pintype "passive"))
      (node (ref "U0-C") (pin "99") (pinfunction "PC9_99") (pintype "bidirectional"))
      (node (ref "U2-C") (pin "9") (pinfunction "SDA_9") (pintype "bidirectional"))
    )
    (net (code "128") (name "SENSE_A") (class "Default")
      (node (ref "J3-CP") (pin "1") (pinfunction "1_1") (pintype "passive"))
      (node (ref "R3-5P") (pin "2") (pinfunction "2_2") (pintype "passive"))
      (node (ref "R4-5P") (pin "2") (pinfunction "2_2") (pintype "passive"))
      (node (ref "U0-C") (pin "18") (pinfunction "PF6_18") (pintype "bidirectional"))
      (node (ref "U2-C") (pin "4") (pinfunction "AIN0_4") (pintype "bidirectional"))
    )
    (net (code "129") (name "SENSE_B") (class "Default")
      (node (ref "J3-CP") (pin "2") (pinfunction "2_2") (pintype "passive"))
      (node (ref "R7-5P") (pin "2") (pinfunction "2_2") (pintype "passive"))
      (node (ref "R8-5P") (pin "2") (pinfunction "2_2") (pintype "passive"))
      (node (ref "U0-C") (pin "19") (pinfunction "PF7_19") (pintype "bidirectional"))
      (node (ref "U2-C") (pin "5") (pinfunction "AIN1_5") (pintype "bidirectional"))
    )
    (net (code "130") (name "SENSE_C") (class "Default")
      (node (ref "J3-CP") (pin "3") (pinfunction "3_3") (pintype "passive"))
      (node (ref "R3-6P") (pin "2") (pinfunction "2_2") (pintype "passive"))
      (node (ref "R4-6P") (pin "2") (pinfunction "2_2") (pintype "passive"))
      (node (ref "U0-C") (pin "20") (pinfunction "PF8_20") (pintype "bidirectional"))
      (node (ref "U2-C") (pin "6") (pinfunction "AIN2_6") (pintype "bidirectional"))
    )
    (net (code "131") (name "SENSE_D") (class "Default")
      (node (ref "J3-CP") (pin "4") (pinfunction "4_4") (pintype "passive"))
      (node (ref "R7-6P") (pin "2") (pinfunction "2_2") (pintype "passive"))
      (node (ref "R8-6P") (pin "2") (pinfunction "2_2") (pintype "passive"))
      (node (ref "U0-C") (pin "21") (pinfunction "PF9_21") (pintype "bidirectional"))
      (node (ref "U2-C") (pin "7") (pinfunction "AIN3_7") (pintype "bidirectional"))
    )
    (net (code "132") (name "SENSOR-ERROR") (class "Default")
      (node (ref "D2A-S") (pin "A") (pinfunction "A_A") (pintype "passive"))
      (node (ref "D2B-S") (pin "A") (pinfunction "A_A") (pintype "passive"))
      (node (ref "U0-C") (pin "64") (pinfunction "PE11_64") (pintype "bidirectional"))
    )
    (net (code "133") (name "SENSOR-NOMINAL") (class "Default")
      (node (ref "D1A-S") (pin "A") (pinfunction "A_A") (pintype "passive"))
      (node (ref "D1B-S") (pin "A") (pinfunction "A_A") (pintype "passive"))
      (node (ref "U0-C") (pin "63") (pinfunction "PE10_63") (pintype "bidirectional"))
    )
    (net (code "134") (name "STORAGE-ERROR") (class "Default")
      (node (ref "D5-C") (pin "A") (pinfunction "A_A") (pintype "passive"))
      (node (ref "U0-C") (pin "58") (pinfunction "PE7_58") (pintype "bidirectional"))
    )
    (net (code "135") (name "SWCLK") (class "Default")
      (node (ref "J1-C") (pin "2") (pinfunction "2_2") (pintype "passive"))
      (node (ref "R4-J1C") (pin "1") (pinfunction "1_1") (pintype "passive"))
      (node (ref "R4-J1C") (pin "2") (pinfunction "2_2") (pintype "passive"))
      (node (ref "U0-C") (pin "109") (pinfunction "PA14_109") (pintype "bidirectional"))
    )
    (net (code "136") (name "SWDIO") (class "Default")
      (node (ref "J1-C") (pin "3") (pinfunction "3_3") (pintype "passive"))
      (node (ref "R3-J1C") (pin "1") (pinfunction "1_1") (pintype "passive"))
      (node (ref "R3-J1C") (pin "2") (pinfunction "2_2") (pintype "passive"))
      (node (ref "U0-C") (pin "105") (pinfunction "PA13_105") (pintype "bidirectional"))
    )
    (net (code "137") (name "SWO") (class "Default")
      (node (ref "R1-J1C") (pin "2") (pinfunction "2_2") (pintype "passive"))
      (node (ref "U0-C") (pin "133") (pinfunction "PB3_133") (pintype "bidirectional"))
    )
    (net (code "138") (name "U1S-CHECK") (class "Default")
      (node (ref "D2-1S") (pin "A") (pinfunction "A_A") (pintype "passive"))
      (node (ref "J3-CS") (pin "3") (pinfunction "3_3") (pintype "passive"))
      (node (ref "U0-C") (pin "65") (pinfunction "PE12_65") (pintype "bidirectional"))
    )
    (net (code "139") (name "U2P-FB") (class "Default")
      (node (ref "C3-2P") (pin "2") (pinfunction "2_2") (pintype "passive"))
      (node (ref "R1-2P") (pin "1") (pinfunction "1_1") (pintype "passive"))
      (node (ref "R2-2P") (pin "2") (pinfunction "2_2") (pintype "passive"))
      (node (ref "U2-P") (pin "15") (pinfunction "FB_15") (pintype "bidirectional"))
    )
    (net (code "140") (name "U2S-CHECK") (class "Default")
      (node (ref "D2-2S") (pin "A") (pinfunction "A_A") (pintype "passive"))
      (node (ref "J3-CS") (pin "4") (pinfunction "4_4") (pintype "passive"))
      (node (ref "U0-C") (pin "66") (pinfunction "PE13_66") (pintype "bidirectional"))
    )
    (net (code "141") (name "U2S-ST") (class "Default")
      (node (ref "J3-CS") (pin "7") (pinfunction "7_7") (pintype "passive"))
      (node (ref "U0-C") (pin "69") (pinfunction "PB10_69") (pintype "bidirectional"))
      (node (ref "U2-S") (pin "4") (pinfunction "ST_4") (pintype "bidirectional"))
    )
    (net (code "143") (name "U3S-CHECK") (class "Default")
      (node (ref "D2-3S") (pin "A") (pinfunction "A_A") (pintype "passive"))
      (node (ref "J3-CS") (pin "5") (pinfunction "5_5") (pintype "passive"))
      (node (ref "U0-C") (pin "67") (pinfunction "PE14_67") (pintype "bidirectional"))
    )
    (net (code "145") (name "U4S-CHECK") (class "Default")
      (node (ref "D2-4S") (pin "A") (pinfunction "A_A") (pintype "passive"))
      (node (ref "J3-CS") (pin "6") (pinfunction "6_6") (pintype "passive"))
      (node (ref "U0-C") (pin "68") (pinfunction "PE15_68") (pintype "bidirectional"))
    )
    (net (code "146") (name "U9P-FB") (class "Default")
      (node (ref "C1-9P") (pin "2") (pinfunction "2_2") (pintype "passive"))
      (node (ref "C2-9P") (pin "1") (pinfunction "1_1") (pintype "passive"))
      (node (ref "R1-9P") (pin "1") (pinfunction "1_1") (pintype "passive"))
      (node (ref "R2-9P") (pin "2") (pinfunction "2_2") (pintype "passive"))
      (node (ref "U9-P") (pin "4") (pinfunction "FB_4") (pintype "bidirectional"))
    )
    (net (code "147") (name "U9P-SW") (class "Default")
      (node (ref "L1-9P") (pin "1") (pinfunction "1_1") (pintype "bidirectional"))
      (node (ref "U9-P") (pin "5") (pinfunction "SW_5") (pintype "bidirectional"))
    )
    (net (code "148") (name "US2-STATUS") (class "Default")
      (node (ref "J3-CS") (pin "8") (pinfunction "8_8") (pintype "passive"))
      (node (ref "U0-C") (pin "70") (pinfunction "PB11_70") (pintype "bidirectional"))
      (node (ref "U2-S") (pin "6") (pinfunction "STATUS_6") (pintype "bidirectional"))
    )
    (net (code "149") (name "VBAT") (class "Default")
      (node (ref "1S_LIPO") (pin "1") (pinfunction "1_1") (pintype "bidirectional"))
      (node (ref "C2-1P") (pin "1") (pinfunction "1_1") (pintype "passive"))
      (node (ref "J2-P") (pin "1") (pinfunction "1_1") (pintype "bidirectional"))
      (node (ref "J2-P") (pin "3") (pinfunction "3_3") (pintype "bidirectional"))
      (node (ref "J2-P") (pin "5") (pinfunction "5_5") (pintype "bidirectional"))
      (node (ref "J2-P") (pin "7") (pinfunction "7_7") (pintype "bidirectional"))
      (node (ref "S1-P") (pin "P") (pinfunction "P_P") (pintype "passive"))
      (node (ref "U1-P") (pin "3") (pinfunction "VBAT_3") (pintype "bidirectional"))
    )
    (net (code "150") (name "VDDA") (class "Default")
      (node (ref "FB1-0C") (pin "2") (pinfunction "2_2") (pintype "bidirectional"))
      (node (ref "U0-C") (pin "32") (pinfunction "VREF+_32") (pintype "input"))
      (node (ref "U0-C") (pin "33") (pinfunction "VDDA_33") (pintype "power_in"))
    )
    (net (code "151") (name "VUSB") (class "Default")
      (node (ref "C1-1P") (pin "1") (pinfunction "1_1") (pintype "passive"))
      (node (ref "D1-1P") (pin "A") (pinfunction "A_A") (pintype "passive"))
      (node (ref "J2-C") (pin "1") (pinfunction "VBUS_1") (pintype "power_in"))
      (node (ref "JP-CP") (pin "4") (pinfunction "4_4") (pintype "passive"))
      (node (ref "U1-P") (pin "4") (pinfunction "VDD_4") (pintype "power_in"))
    )
    (net (code "152") (name "V_LDO_IN") (class "Default")
      (node (ref "C1-11P") (pin "1") (pinfunction "1_1") (pintype "passive"))
      (node (ref "C1-2P") (pin "1") (pinfunction "1_1") (pintype "passive"))
      (node (ref "C2-2P") (pin "1") (pinfunction "1_1") (pintype "passive"))
      (node (ref "D1-11P") (pin "1") (pinfunction "K_1") (pintype "bidirectional"))
      (node (ref "R1-11P") (pin "2") (pinfunction "2_2") (pintype "passive"))
      (node (ref "U2-P") (pin "10") (pinfunction "VIN_10") (pintype "bidirectional"))
      (node (ref "U2-P") (pin "11") (pinfunction "EN_11") (pintype "bidirectional"))
      (node (ref "U2-P") (pin "6") (pinfunction "PVIN_1_6") (pintype "bidirectional"))
      (node (ref "U2-P") (pin "7") (pinfunction "PVIN_2_7") (pintype "bidirectional"))
      (node (ref "U2-P") (pin "8") (pinfunction "PVIN_3_8") (pintype "bidirectional"))
      (node (ref "U2-P") (pin "9") (pinfunction "PVIN_4_9") (pintype "bidirectional"))
    )
    (net (code "153") (name "WP") (class "Default")
      (node (ref "U0-C") (pin "78") (pinfunction "PD9_78") (pintype "bidirectional"))
      (node (ref "U1-C") (pin "3") (pinfunction "~{WP}/IO2_3") (pintype "bidirectional"))
    )
    (net (code "154") (name "unconnected-(J1-9P-Pad1)") (class "Default")
      (node (ref "J1-9P") (pin "1") (pinfunction "1_1") (pintype "passive"))
    )
    (net (code "155") (name "unconnected-(J1-9P-Pad2)") (class "Default")
      (node (ref "J1-9P") (pin "2") (pinfunction "2_2") (pintype "passive"))
    )
    (net (code "156") (name "unconnected-(J1-9P-Pad3)") (class "Default")
      (node (ref "J1-9P") (pin "3") (pinfunction "3_3") (pintype "passive"))
    )
    (net (code "157") (name "unconnected-(J1-9P-Pad4)") (class "Default")
      (node (ref "J1-9P") (pin "4") (pinfunction "4_4") (pintype "passive"))
    )
    (net (code "158") (name "unconnected-(J1-9P-Pad6)") (class "Default")
      (node (ref "J1-9P") (pin "6") (pinfunction "6_6") (pintype "passive"))
    )
    (net (code "159") (name "unconnected-(J1-9P-Pad8)") (class "Default")
      (node (ref "J1-9P") (pin "8") (pinfunction "8_8") (pintype "passive"))
    )
    (net (code "160") (name "unconnected-(J1-9P-Pad10)") (class "Default")
      (node (ref "J1-9P") (pin "10") (pinfunction "10_10") (pintype "passive"))
    )
    (net (code "161") (name "unconnected-(J1-9P-Pad11)") (class "Default")
      (node (ref "J1-9P") (pin "11") (pinfunction "11_11") (pintype "passive"))
    )
    (net (code "162") (name "unconnected-(J1-9P-Pad12)") (class "Default")
      (node (ref "J1-9P") (pin "12") (pinfunction "12_12") (pintype "passive"))
    )
    (net (code "163") (name "unconnected-(J1-9P-Pad16)") (class "Default")
      (node (ref "J1-9P") (pin "16") (pinfunction "16_16") (pintype "passive"))
    )
    (net (code "164") (name "unconnected-(JP-CS-Pad4)") (class "Default")
      (node (ref "JP-CS") (pin "4") (pinfunction "4_4") (pintype "passive"))
    )
    (net (code "165") (name "unconnected-(S0-0C-P1-Pad4)") (class "Default")
      (node (ref "S0-0C") (pin "4") (pinfunction "P1_4") (pintype "passive"))
    )
    (net (code "166") (name "unconnected-(S0-0C-S1-Pad2)") (class "Default")
      (node (ref "S0-0C") (pin "2") (pinfunction "S1_2") (pintype "passive"))
    )
    (net (code "167") (name "unconnected-(S1-P-PadO)") (class "Default")
      (node (ref "S1-P") (pin "O") (pinfunction "O_O") (pintype "passive"))
    )
    (net (code "168") (name "unconnected-(U0-C-PA4-Pad40)") (class "Default")
      (node (ref "U0-C") (pin "40") (pinfunction "PA4_40") (pintype "bidirectional"))
    )
    (net (code "169") (name "unconnected-(U0-C-PA9-Pad101)") (class "Default")
      (node (ref "U0-C") (pin "101") (pinfunction "PA9_101") (pintype "bidirectional"))
    )
    (net (code "170") (name "unconnected-(U0-C-PA15-Pad110)") (class "Default")
      (node (ref "U0-C") (pin "110") (pinfunction "PA15_110") (pintype "bidirectional"))
    )
    (net (code "171") (name "unconnected-(U0-C-PB2-Pad48)") (class "Default")
      (node (ref "U0-C") (pin "48") (pinfunction "PB2_48") (pintype "bidirectional"))
    )
    (net (code "172") (name "unconnected-(U0-C-PB4-Pad134)") (class "Default")
      (node (ref "U0-C") (pin "134") (pinfunction "PB4_134") (pintype "bidirectional"))
    )
    (net (code "173") (name "unconnected-(U0-C-PB5-Pad135)") (class "Default")
      (node (ref "U0-C") (pin "135") (pinfunction "PB5_135") (pintype "bidirectional"))
    )
    (net (code "174") (name "unconnected-(U0-C-PB6-Pad136)") (class "Default")
      (node (ref "U0-C") (pin "136") (pinfunction "PB6_136") (pintype "bidirectional"))
    )
    (net (code "175") (name "unconnected-(U0-C-PB7-Pad137)") (class "Default")
      (node (ref "U0-C") (pin "137") (pinfunction "PB7_137") (pintype "bidirectional"))
    )
    (net (code "176") (name "unconnected-(U0-C-PB8-Pad139)") (class "Default")
      (node (ref "U0-C") (pin "139") (pinfunction "PB8_139") (pintype "bidirectional"))
    )
    (net (code "177") (name "unconnected-(U0-C-PB9-Pad140)") (class "Default")
      (node (ref "U0-C") (pin "140") (pinfunction "PB9_140") (pintype "bidirectional"))
    )
    (net (code "178") (name "unconnected-(U0-C-PB12-Pad73)") (class "Default")
      (node (ref "U0-C") (pin "73") (pinfunction "PB12_73") (pintype "bidirectional"))
    )
    (net (code "179") (name "unconnected-(U0-C-PB13-Pad74)") (class "Default")
      (node (ref "U0-C") (pin "74") (pinfunction "PB13_74") (pintype "bidirectional"))
    )
    (net (code "180") (name "unconnected-(U0-C-PB14-Pad75)") (class "Default")
      (node (ref "U0-C") (pin "75") (pinfunction "PB14_75") (pintype "bidirectional"))
    )
    (net (code "181") (name "unconnected-(U0-C-PB15-Pad76)") (class "Default")
      (node (ref "U0-C") (pin "76") (pinfunction "PB15_76") (pintype "bidirectional"))
    )
    (net (code "182") (name "unconnected-(U0-C-PC0-Pad26)") (class "Default")
      (node (ref "U0-C") (pin "26") (pinfunction "PC0_26") (pintype "bidirectional"))
    )
    (net (code "183") (name "unconnected-(U0-C-PC1-Pad27)") (class "Default")
      (node (ref "U0-C") (pin "27") (pinfunction "PC1_27") (pintype "bidirectional"))
    )
    (net (code "184") (name "unconnected-(U0-C-PC2-Pad28)") (class "Default")
      (node (ref "U0-C") (pin "28") (pinfunction "PC2_28") (pintype "bidirectional"))
    )
    (net (code "185") (name "unconnected-(U0-C-PC3-Pad29)") (class "Default")
      (node (ref "U0-C") (pin "29") (pinfunction "PC3_29") (pintype "bidirectional"))
    )
    (net (code "186") (name "unconnected-(U0-C-PC13-Pad7)") (class "Default")
      (node (ref "U0-C") (pin "7") (pinfunction "PC13_7") (pintype "bidirectional"))
    )
    (net (code "187") (name "unconnected-(U0-C-PC14-Pad8)") (class "Default")
      (node (ref "U0-C") (pin "8") (pinfunction "PC14_8") (pintype "bidirectional"))
    )
    (net (code "188") (name "unconnected-(U0-C-PC15-Pad9)") (class "Default")
      (node (ref "U0-C") (pin "9") (pinfunction "PC15_9") (pintype "bidirectional"))
    )
    (net (code "189") (name "unconnected-(U0-C-PD1-Pad115)") (class "Default")
      (node (ref "U0-C") (pin "115") (pinfunction "PD1_115") (pintype "bidirectional"))
    )
    (net (code "190") (name "unconnected-(U0-C-PD2-Pad116)") (class "Default")
      (node (ref "U0-C") (pin "116") (pinfunction "PD2_116") (pintype "bidirectional"))
    )
    (net (code "191") (name "unconnected-(U0-C-PD3-Pad117)") (class "Default")
      (node (ref "U0-C") (pin "117") (pinfunction "PD3_117") (pintype "bidirectional"))
    )
    (net (code "192") (name "unconnected-(U0-C-PD4-Pad118)") (class "Default")
      (node (ref "U0-C") (pin "118") (pinfunction "PD4_118") (pintype "bidirectional"))
    )
    (net (code "193") (name "unconnected-(U0-C-PD5-Pad119)") (class "Default")
      (node (ref "U0-C") (pin "119") (pinfunction "PD5_119") (pintype "bidirectional"))
    )
    (net (code "194") (name "unconnected-(U0-C-PD6-Pad122)") (class "Default")
      (node (ref "U0-C") (pin "122") (pinfunction "PD6_122") (pintype "bidirectional"))
    )
    (net (code "195") (name "unconnected-(U0-C-PD7-Pad123)") (class "Default")
      (node (ref "U0-C") (pin "123") (pinfunction "PD7_123") (pintype "bidirectional"))
    )
    (net (code "196") (name "unconnected-(U0-C-PD10-Pad79)") (class "Default")
      (node (ref "U0-C") (pin "79") (pinfunction "PD10_79") (pintype "bidirectional"))
    )
    (net (code "197") (name "unconnected-(U0-C-PD11-Pad80)") (class "Default")
      (node (ref "U0-C") (pin "80") (pinfunction "PD11_80") (pintype "bidirectional"))
    )
    (net (code "198") (name "unconnected-(U0-C-PD12-Pad81)") (class "Default")
      (node (ref "U0-C") (pin "81") (pinfunction "PD12_81") (pintype "bidirectional"))
    )
    (net (code "199") (name "unconnected-(U0-C-PD13-Pad82)") (class "Default")
      (node (ref "U0-C") (pin "82") (pinfunction "PD13_82") (pintype "bidirectional"))
    )
    (net (code "200") (name "unconnected-(U0-C-PD14-Pad85)") (class "Default")
      (node (ref "U0-C") (pin "85") (pinfunction "PD14_85") (pintype "bidirectional"))
    )
    (net (code "201") (name "unconnected-(U0-C-PD15-Pad86)") (class "Default")
      (node (ref "U0-C") (pin "86") (pinfunction "PD15_86") (pintype "bidirectional"))
    )
    (net (code "202") (name "unconnected-(U0-C-PE0-Pad141)") (class "Default")
      (node (ref "U0-C") (pin "141") (pinfunction "PE0_141") (pintype "bidirectional"))
    )
    (net (code "203") (name "unconnected-(U0-C-PE1-Pad142)") (class "Default")
      (node (ref "U0-C") (pin "142") (pinfunction "PE1_142") (pintype "bidirectional"))
    )
    (net (code "204") (name "unconnected-(U0-C-PE3-Pad2)") (class "Default")
      (node (ref "U0-C") (pin "2") (pinfunction "PE3_2") (pintype "bidirectional"))
    )
    (net (code "205") (name "unconnected-(U0-C-PE4-Pad3)") (class "Default")
      (node (ref "U0-C") (pin "3") (pinfunction "PE4_3") (pintype "bidirectional"))
    )
    (net (code "206") (name "unconnected-(U0-C-PE5-Pad4)") (class "Default")
      (node (ref "U0-C") (pin "4") (pinfunction "PE5_4") (pintype "bidirectional"))
    )
    (net (code "207") (name "unconnected-(U0-C-PE6-Pad5)") (class "Default")
      (node (ref "U0-C") (pin "5") (pinfunction "PE6_5") (pintype "bidirectional"))
    )
    (net (code "208") (name "unconnected-(U0-C-PE9-Pad60)") (class "Default")
      (node (ref "U0-C") (pin "60") (pinfunction "PE9_60") (pintype "bidirectional"))
    )
    (net (code "209") (name "unconnected-(U0-C-PF0-Pad10)") (class "Default")
      (node (ref "U0-C") (pin "10") (pinfunction "PF0_10") (pintype "bidirectional"))
    )
    (net (code "210") (name "unconnected-(U0-C-PF5-Pad15)") (class "Default")
      (node (ref "U0-C") (pin "15") (pinfunction "PF5_15") (pintype "bidirectional"))
    )
    (net (code "211") (name "unconnected-(U0-C-PF10-Pad22)") (class "Default")
      (node (ref "U0-C") (pin "22") (pinfunction "PF10_22") (pintype "bidirectional"))
    )
    (net (code "212") (name "unconnected-(U0-C-PF11-Pad49)") (class "Default")
      (node (ref "U0-C") (pin "49") (pinfunction "PF11_49") (pintype "bidirectional"))
    )
    (net (code "213") (name "unconnected-(U0-C-PF12-Pad50)") (class "Default")
      (node (ref "U0-C") (pin "50") (pinfunction "PF12_50") (pintype "bidirectional"))
    )
    (net (code "214") (name "unconnected-(U0-C-PG2-Pad87)") (class "Default")
      (node (ref "U0-C") (pin "87") (pinfunction "PG2_87") (pintype "bidirectional"))
    )
    (net (code "215") (name "unconnected-(U0-C-PG3-Pad88)") (class "Default")
      (node (ref "U0-C") (pin "88") (pinfunction "PG3_88") (pintype "bidirectional"))
    )
    (net (code "216") (name "unconnected-(U0-C-PG5-Pad90)") (class "Default")
      (node (ref "U0-C") (pin "90") (pinfunction "PG5_90") (pintype "bidirectional"))
    )
    (net (code "217") (name "unconnected-(U0-C-PG6-Pad91)") (class "Default")
      (node (ref "U0-C") (pin "91") (pinfunction "PG6_91") (pintype "bidirectional"))
    )
    (net (code "218") (name "unconnected-(U0-C-PG7-Pad92)") (class "Default")
      (node (ref "U0-C") (pin "92") (pinfunction "PG7_92") (pintype "bidirectional"))
    )
    (net (code "219") (name "unconnected-(U0-C-PG8-Pad93)") (class "Default")
      (node (ref "U0-C") (pin "93") (pinfunction "PG8_93") (pintype "bidirectional"))
    )
    (net (code "220") (name "unconnected-(U0-C-PG9-Pad124)") (class "Default")
      (node (ref "U0-C") (pin "124") (pinfunction "PG9_124") (pintype "bidirectional"))
    )
    (net (code "221") (name "unconnected-(U0-C-PG10-Pad125)") (class "Default")
      (node (ref "U0-C") (pin "125") (pinfunction "PG10_125") (pintype "bidirectional"))
    )
    (net (code "222") (name "unconnected-(U0-C-PG11-Pad126)") (class "Default")
      (node (ref "U0-C") (pin "126") (pinfunction "PG11_126") (pintype "bidirectional"))
    )
    (net (code "223") (name "unconnected-(U0-C-PG12-Pad127)") (class "Default")
      (node (ref "U0-C") (pin "127") (pinfunction "PG12_127") (pintype "bidirectional"))
    )
    (net (code "224") (name "unconnected-(U0-C-PG13-Pad128)") (class "Default")
      (node (ref "U0-C") (pin "128") (pinfunction "PG13_128") (pintype "bidirectional"))
    )
    (net (code "225") (name "unconnected-(U0-C-PG14-Pad129)") (class "Default")
      (node (ref "U0-C") (pin "129") (pinfunction "PG14_129") (pintype "bidirectional"))
    )
    (net (code "226") (name "unconnected-(U0-C-PG15-Pad132)") (class "Default")
      (node (ref "U0-C") (pin "132") (pinfunction "PG15_132") (pintype "bidirectional"))
    )
    (net (code "227") (name "unconnected-(U1-C-EP-Pad9)") (class "Default")
      (node (ref "U1-C") (pin "9") (pinfunction "EP_9") (pintype "bidirectional"))
    )
    (net (code "228") (name "unconnected-(U1-S-AUX_CL-Pad7)") (class "Default")
      (node (ref "U1-S") (pin "7") (pinfunction "AUX_CL_7") (pintype "bidirectional"))
    )
    (net (code "229") (name "unconnected-(U1-S-AUX_DA-Pad21)") (class "Default")
      (node (ref "U1-S") (pin "21") (pinfunction "AUX_DA_21") (pintype "bidirectional"))
    )
    (net (code "230") (name "unconnected-(U1-S-FSYNC-Pad11)") (class "Default")
      (node (ref "U1-S") (pin "11") (pinfunction "FSYNC_11") (pintype "bidirectional"))
    )
    (net (code "231") (name "unconnected-(U1-S-INT1-Pad12)") (class "Default")
      (node (ref "U1-S") (pin "12") (pinfunction "INT1_12") (pintype "bidirectional"))
    )
    (net (code "232") (name "unconnected-(U1-S-NC.1-Pad1)") (class "Default")
      (node (ref "U1-S") (pin "1") (pinfunction "NC.1_1") (pintype "bidirectional"))
    )
    (net (code "233") (name "unconnected-(U1-S-NC.2-Pad2)") (class "Default")
      (node (ref "U1-S") (pin "2") (pinfunction "NC.2_2") (pintype "bidirectional"))
    )
    (net (code "234") (name "unconnected-(U1-S-NC.3-Pad3)") (class "Default")
      (node (ref "U1-S") (pin "3") (pinfunction "NC.3_3") (pintype "bidirectional"))
    )
    (net (code "235") (name "unconnected-(U1-S-NC.4-Pad4)") (class "Default")
      (node (ref "U1-S") (pin "4") (pinfunction "NC.4_4") (pintype "bidirectional"))
    )
    (net (code "236") (name "unconnected-(U1-S-NC.5-Pad5)") (class "Default")
      (node (ref "U1-S") (pin "5") (pinfunction "NC.5_5") (pintype "bidirectional"))
    )
    (net (code "237") (name "unconnected-(U1-S-NC.6-Pad6)") (class "Default")
      (node (ref "U1-S") (pin "6") (pinfunction "NC.6_6") (pintype "bidirectional"))
    )
    (net (code "238") (name "unconnected-(U1-S-NC.14-Pad14)") (class "Default")
      (node (ref "U1-S") (pin "14") (pinfunction "NC.14_14") (pintype "bidirectional"))
    )
    (net (code "239") (name "unconnected-(U1-S-NC.15-Pad15)") (class "Default")
      (node (ref "U1-S") (pin "15") (pinfunction "NC.15_15") (pintype "bidirectional"))
    )
    (net (code "240") (name "unconnected-(U1-S-NC.16-Pad16)") (class "Default")
      (node (ref "U1-S") (pin "16") (pinfunction "NC.16_16") (pintype "bidirectional"))
    )
    (net (code "241") (name "unconnected-(U1-S-NC.17-Pad17)") (class "Default")
      (node (ref "U1-S") (pin "17") (pinfunction "NC.17_17") (pintype "bidirectional"))
    )
    (net (code "242") (name "unconnected-(U1-S-RESV.NC-Pad19)") (class "Default")
      (node (ref "U1-S") (pin "19") (pinfunction "RESV.NC_19") (pintype "bidirectional"))
    )
    (net (code "243") (name "unconnected-(U2-P-EP-Pad21)") (class "Default")
      (node (ref "U2-P") (pin "21") (pinfunction "EP_21") (pintype "bidirectional"))
    )
    (net (code "244") (name "unconnected-(U2-P-LX1_2-Pad5)") (class "Default")
      (node (ref "U2-P") (pin "5") (pinfunction "LX1_2_5") (pintype "bidirectional"))
    )
    (net (code "245") (name "unconnected-(U2-P-LX2_2-Pad2)") (class "Default")
      (node (ref "U2-P") (pin "2") (pinfunction "LX2_2_2") (pintype "bidirectional"))
    )
    (net (code "246") (name "unconnected-(U2-P-NC-Pad16)") (class "Default")
      (node (ref "U2-P") (pin "16") (pinfunction "NC_16") (pintype "no_connect"))
    )
    (net (code "247") (name "unconnected-(U2-P-SGND_2-Pad14)") (class "Default")
      (node (ref "U2-P") (pin "14") (pinfunction "SGND_2_14") (pintype "bidirectional"))
    )
    (net (code "248") (name "unconnected-(U4-S-1PPS-Pad13)") (class "Default")
      (node (ref "U4-S") (pin "13") (pinfunction "1PPS_13") (pintype "bidirectional"))
    )
    (net (code "249") (name "unconnected-(U4-S-NREST-Pad2)") (class "Default")
      (node (ref "U4-S") (pin "2") (pinfunction "NREST_2") (pintype "bidirectional"))
    )
    (net (code "250") (name "unconnected-(U4-S-RTCM-Pad14)") (class "Default")
      (node (ref "U4-S") (pin "14") (pinfunction "RTCM_14") (pintype "bidirectional"))
    )
    (net (code "251") (name "unconnected-(U4-S-VBACKUP-Pad4)") (class "Default")
      (node (ref "U4-S") (pin "4") (pinfunction "VBACKUP_4") (pintype "bidirectional"))
    )
  )
)
